# Relay_Board_Rev1-3_-_Altium.net
KiCad netlist of a schematic drawn in Altium Designer
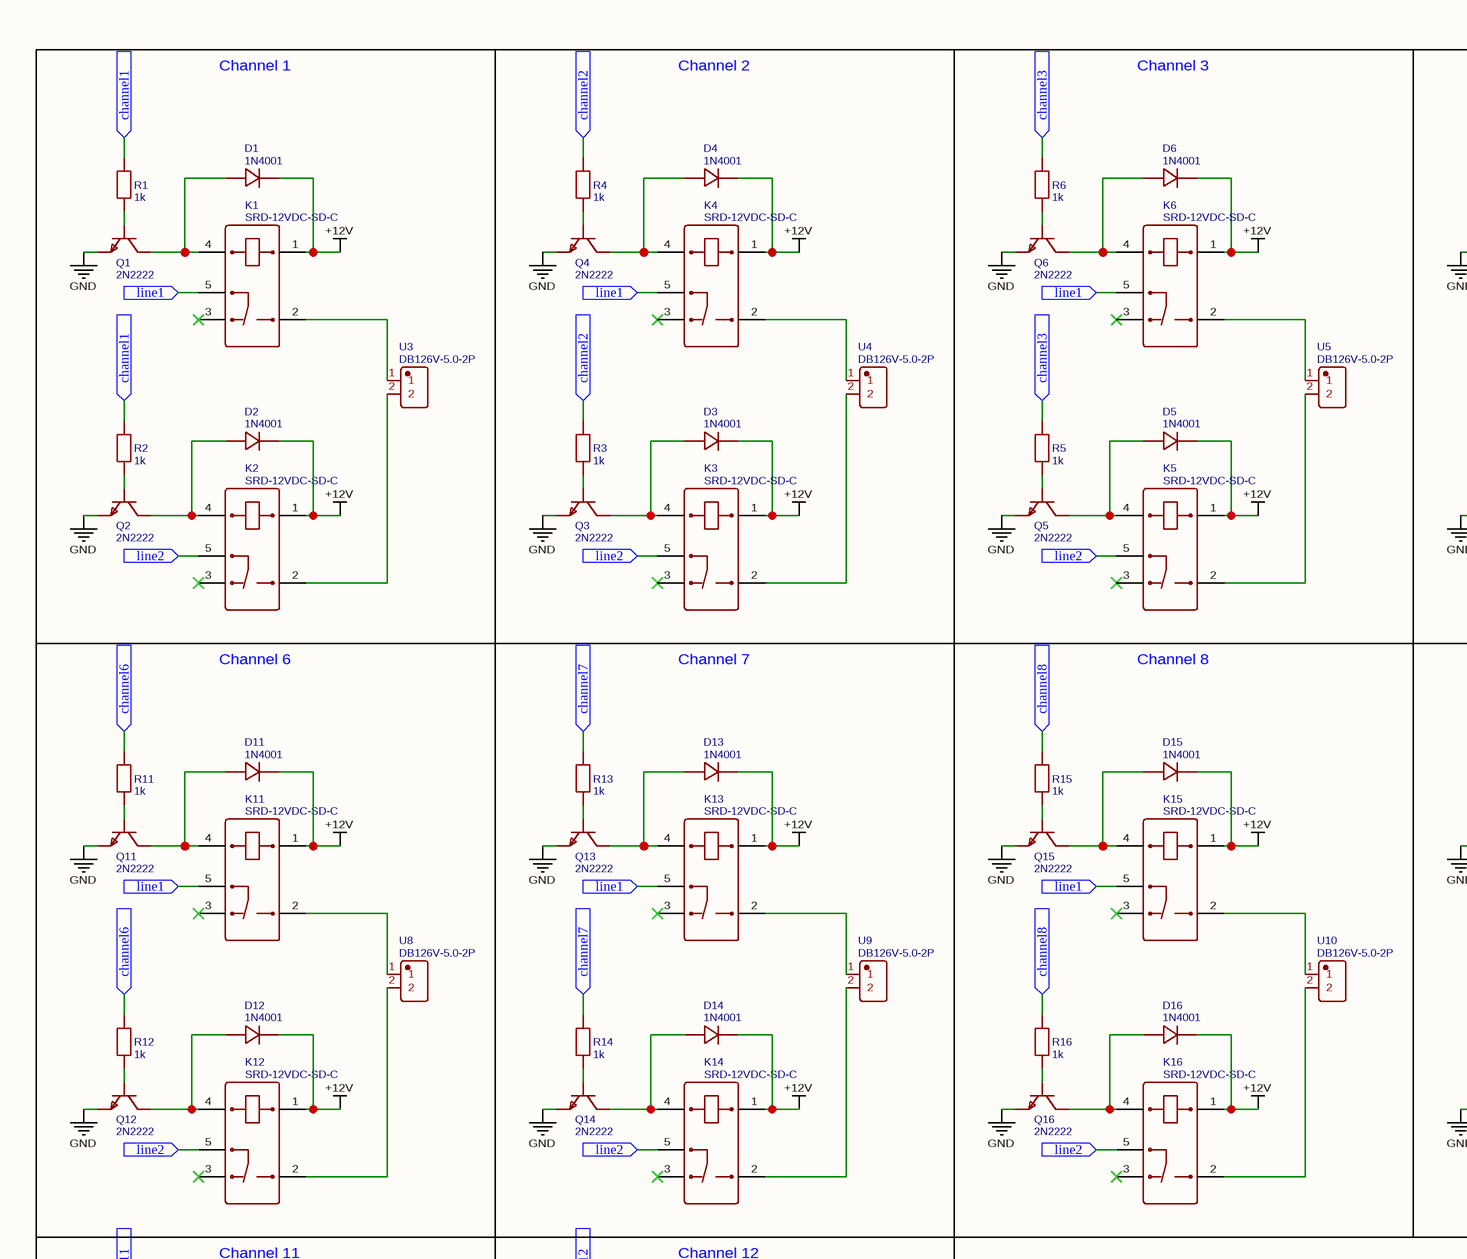
[diagram p0: Relay Board_Rev1-3 - Altium.schdoc, top left]
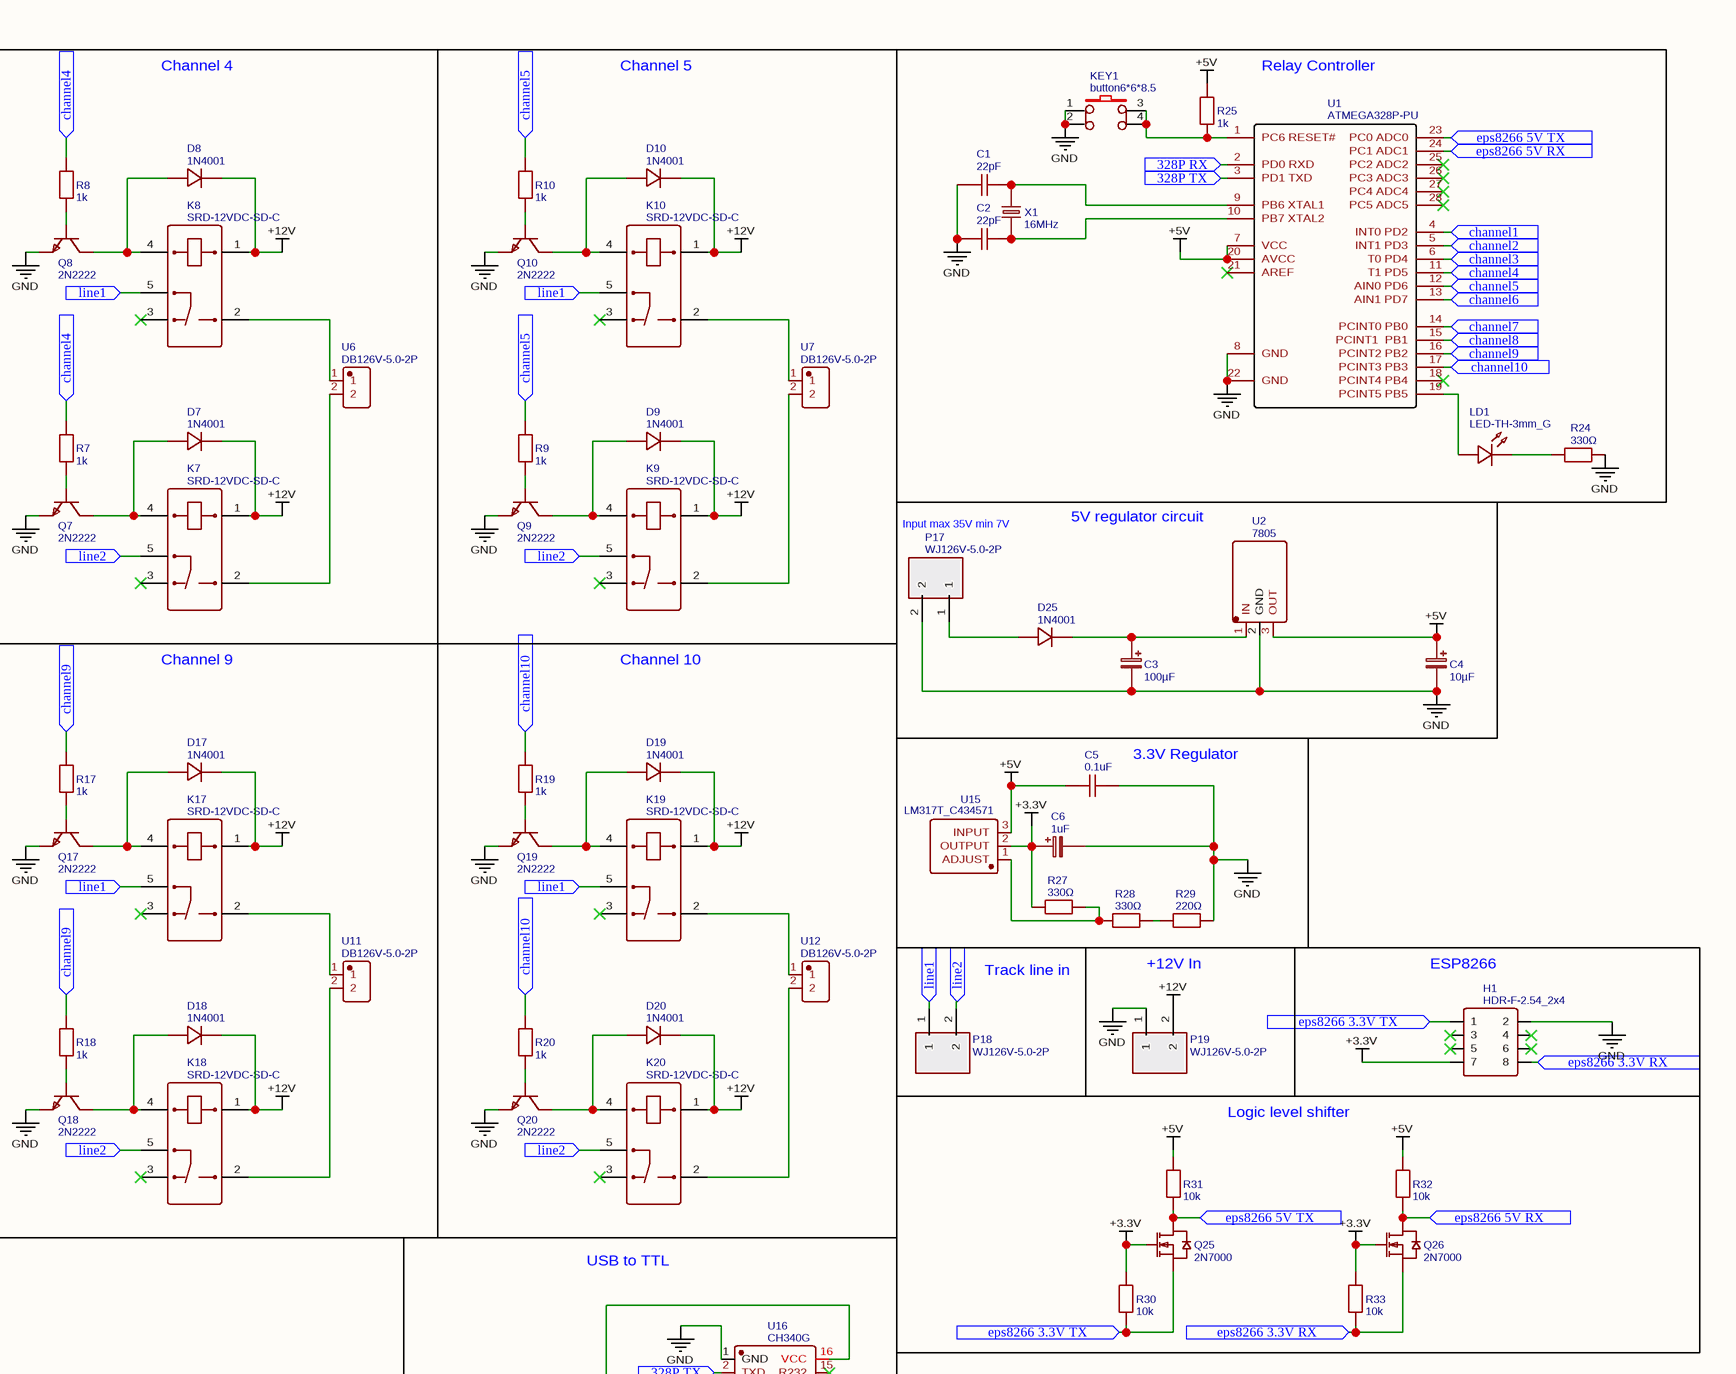
[diagram p1: Relay Board_Rev1-3 - Altium.schdoc, top right]
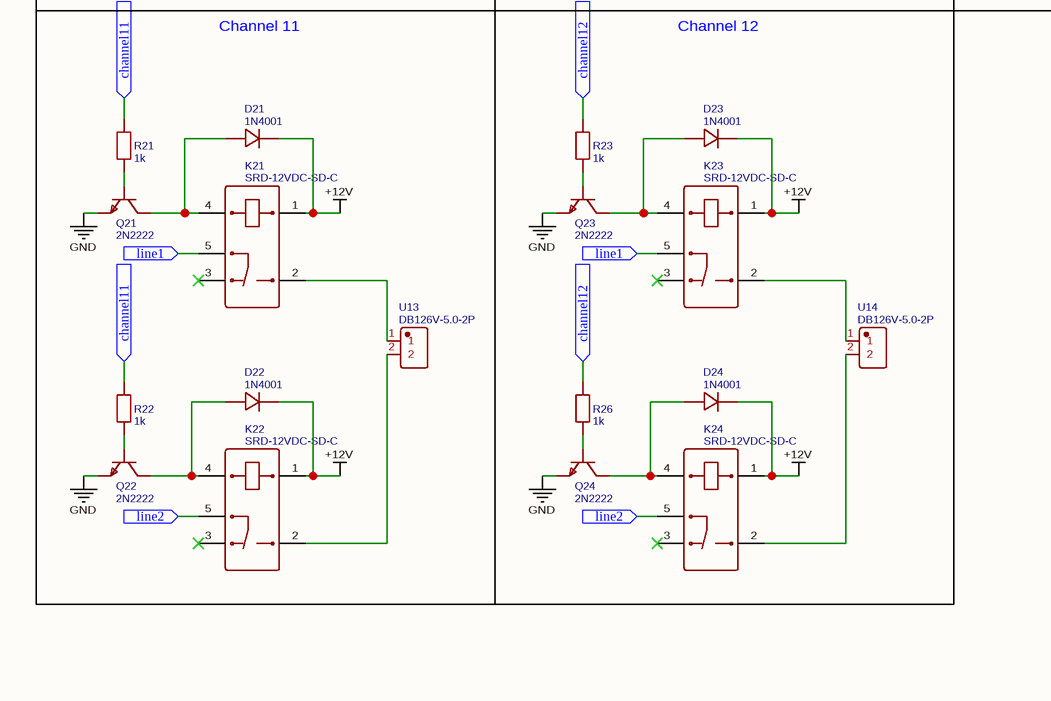
[diagram p2: Relay Board_Rev1-3 - Altium.schdoc, bottom left]
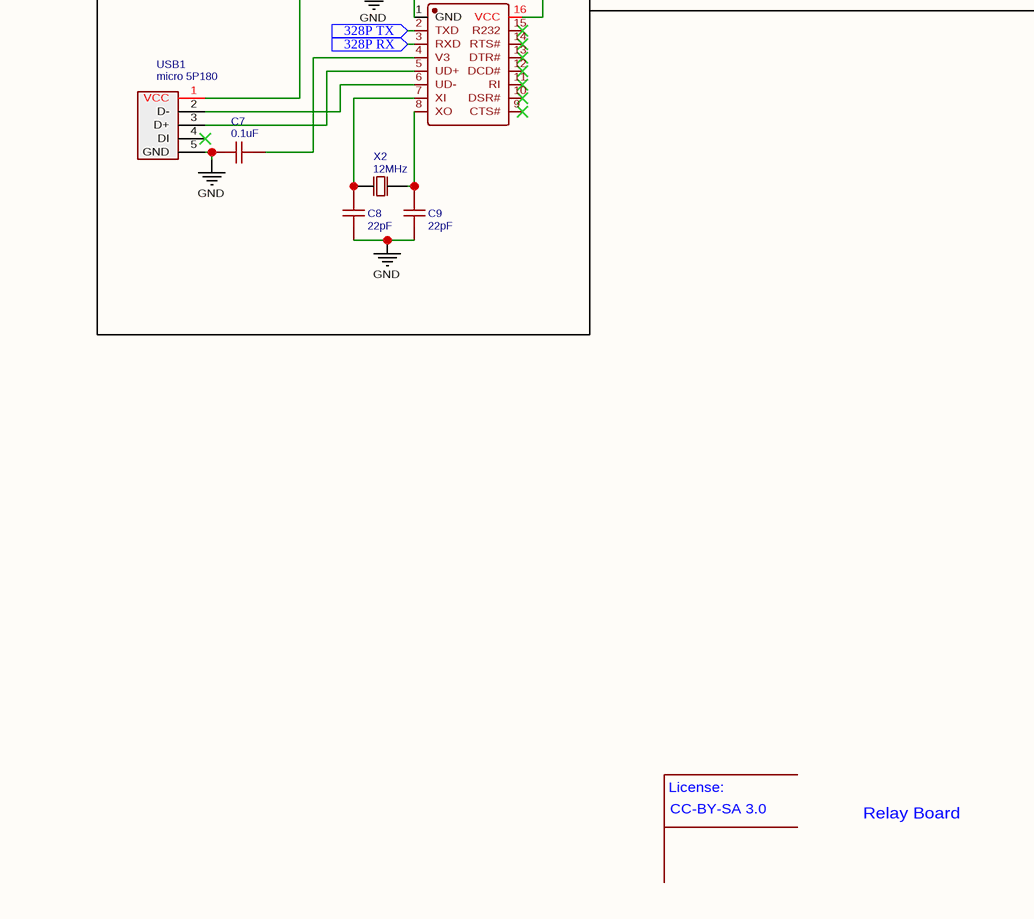
[diagram p3: Relay Board_Rev1-3 - Altium.schdoc, bottom right]

(export (version "E")
  (design (tool "Eeschema 10.0.6"))
  (components
    (comp (ref "C1")
      (value "22pF")
      (fields (field (name "CONTRIBUTOR") "LCEDA_Lib"))
      (libsource (lib "altium-import") (part "root_0_22pF_"))
    )
    (comp (ref "C2")
      (value "22pF")
      (fields (field (name "CONTRIBUTOR") "LCEDA_Lib"))
      (libsource (lib "altium-import") (part "root_0_22pF_"))
    )
    (comp (ref "C3")
      (value "100µF")
      (fields (field (name "CONTRIBUTOR") "LCEDA_Lib"))
      (libsource (lib "altium-import") (part "root_3_100µF_"))
    )
    (comp (ref "C4")
      (value "10µF")
      (fields (field (name "CONTRIBUTOR") "LCEDA_Lib"))
      (libsource (lib "altium-import") (part "root_3_10µF_"))
    )
    (comp (ref "C5")
      (value "0.1uF")
      (fields (field (name "CONTRIBUTOR") "LCEDA_Lib"))
      (libsource (lib "altium-import") (part "root_2_0.1uF_"))
    )
    (comp (ref "C6")
      (value "1uF")
      (fields (field (name "CONTRIBUTOR") "LCEDA_Lib"))
      (libsource (lib "altium-import") (part "root_0_1uF_"))
    )
    (comp (ref "C7")
      (value "0.1uF")
      (fields (field (name "CONTRIBUTOR") "LCEDA_Lib"))
      (libsource (lib "altium-import") (part "root_2_0.1uF_"))
    )
    (comp (ref "C8")
      (value "22pF")
      (fields (field (name "CONTRIBUTOR") "LCEDA_Lib"))
      (libsource (lib "altium-import") (part "root_1_22pF_"))
    )
    (comp (ref "C9")
      (value "22pF")
      (fields (field (name "CONTRIBUTOR") "LCEDA_Lib"))
      (libsource (lib "altium-import") (part "root_1_22pF_"))
    )
    (comp (ref "D1")
      (value "1N4001")
      (fields (field (name "BOM_SUPPLIER PART") "C82804"))
      (libsource (lib "altium-import") (part "root_2_1N4001_"))
    )
    (comp (ref "D2")
      (value "1N4001")
      (fields (field (name "BOM_SUPPLIER PART") "C82804"))
      (libsource (lib "altium-import") (part "root_2_1N4001_"))
    )
    (comp (ref "D3")
      (value "1N4001")
      (fields (field (name "BOM_SUPPLIER PART") "C82804"))
      (libsource (lib "altium-import") (part "root_2_1N4001_"))
    )
    (comp (ref "D4")
      (value "1N4001")
      (fields (field (name "BOM_SUPPLIER PART") "C82804"))
      (libsource (lib "altium-import") (part "root_2_1N4001_"))
    )
    (comp (ref "D5")
      (value "1N4001")
      (fields (field (name "BOM_SUPPLIER PART") "C82804"))
      (libsource (lib "altium-import") (part "root_2_1N4001_"))
    )
    (comp (ref "D6")
      (value "1N4001")
      (fields (field (name "BOM_SUPPLIER PART") "C82804"))
      (libsource (lib "altium-import") (part "root_2_1N4001_"))
    )
    (comp (ref "D7")
      (value "1N4001")
      (fields (field (name "BOM_SUPPLIER PART") "C82804"))
      (libsource (lib "altium-import") (part "root_2_1N4001_"))
    )
    (comp (ref "D8")
      (value "1N4001")
      (fields (field (name "BOM_SUPPLIER PART") "C82804"))
      (libsource (lib "altium-import") (part "root_2_1N4001_"))
    )
    (comp (ref "D9")
      (value "1N4001")
      (fields (field (name "BOM_SUPPLIER PART") "C82804"))
      (libsource (lib "altium-import") (part "root_2_1N4001_"))
    )
    (comp (ref "D10")
      (value "1N4001")
      (fields (field (name "BOM_SUPPLIER PART") "C82804"))
      (libsource (lib "altium-import") (part "root_2_1N4001_"))
    )
    (comp (ref "D11")
      (value "1N4001")
      (fields (field (name "BOM_SUPPLIER PART") "C82804"))
      (libsource (lib "altium-import") (part "root_2_1N4001_"))
    )
    (comp (ref "D12")
      (value "1N4001")
      (fields (field (name "BOM_SUPPLIER PART") "C82804"))
      (libsource (lib "altium-import") (part "root_2_1N4001_"))
    )
    (comp (ref "D13")
      (value "1N4001")
      (fields (field (name "BOM_SUPPLIER PART") "C82804"))
      (libsource (lib "altium-import") (part "root_2_1N4001_"))
    )
    (comp (ref "D14")
      (value "1N4001")
      (fields (field (name "BOM_SUPPLIER PART") "C82804"))
      (libsource (lib "altium-import") (part "root_2_1N4001_"))
    )
    (comp (ref "D15")
      (value "1N4001")
      (fields (field (name "BOM_SUPPLIER PART") "C82804"))
      (libsource (lib "altium-import") (part "root_2_1N4001_"))
    )
    (comp (ref "D16")
      (value "1N4001")
      (fields (field (name "BOM_SUPPLIER PART") "C82804"))
      (libsource (lib "altium-import") (part "root_2_1N4001_"))
    )
    (comp (ref "D17")
      (value "1N4001")
      (fields (field (name "BOM_SUPPLIER PART") "C82804"))
      (libsource (lib "altium-import") (part "root_2_1N4001_"))
    )
    (comp (ref "D18")
      (value "1N4001")
      (fields (field (name "BOM_SUPPLIER PART") "C82804"))
      (libsource (lib "altium-import") (part "root_2_1N4001_"))
    )
    (comp (ref "D19")
      (value "1N4001")
      (fields (field (name "BOM_SUPPLIER PART") "C82804"))
      (libsource (lib "altium-import") (part "root_2_1N4001_"))
    )
    (comp (ref "D20")
      (value "1N4001")
      (fields (field (name "BOM_SUPPLIER PART") "C82804"))
      (libsource (lib "altium-import") (part "root_2_1N4001_"))
    )
    (comp (ref "D21")
      (value "1N4001")
      (fields (field (name "BOM_SUPPLIER PART") "C82804"))
      (libsource (lib "altium-import") (part "root_2_1N4001_"))
    )
    (comp (ref "D22")
      (value "1N4001")
      (fields (field (name "BOM_SUPPLIER PART") "C82804"))
      (libsource (lib "altium-import") (part "root_2_1N4001_"))
    )
    (comp (ref "D23")
      (value "1N4001")
      (fields (field (name "BOM_SUPPLIER PART") "C82804"))
      (libsource (lib "altium-import") (part "root_2_1N4001_"))
    )
    (comp (ref "D24")
      (value "1N4001")
      (fields (field (name "BOM_SUPPLIER PART") "C82804"))
      (libsource (lib "altium-import") (part "root_2_1N4001_"))
    )
    (comp (ref "D25")
      (value "1N4001")
      (fields (field (name "BOM_SUPPLIER PART") "C82804"))
      (libsource (lib "altium-import") (part "root_2_1N4001_"))
    )
    (comp (ref "H1")
      (value "HDR-F-2.54_2x4")
      (fields (field (name "BOM_SUPPLIER PART") "C239344") (field (name "CONTRIBUTOR") "LCEDA_Lib"))
      (libsource (lib "altium-import") (part "root_0_HDR-F-2.54_2x4_"))
    )
    (comp (ref "K1")
      (value "SRD-12VDC-SD-C")
      (fields (field (name "BOM_SUPPLIER PART") "C247843") (field (name "CONTRIBUTOR") "LCSC"))
      (libsource (lib "altium-import") (part "root_2_SRD-12VDC-SD-C_"))
    )
    (comp (ref "K2")
      (value "SRD-12VDC-SD-C")
      (fields (field (name "BOM_SUPPLIER PART") "C247843") (field (name "CONTRIBUTOR") "LCSC"))
      (libsource (lib "altium-import") (part "root_2_SRD-12VDC-SD-C_"))
    )
    (comp (ref "K3")
      (value "SRD-12VDC-SD-C")
      (fields (field (name "BOM_SUPPLIER PART") "C247843") (field (name "CONTRIBUTOR") "LCSC"))
      (libsource (lib "altium-import") (part "root_2_SRD-12VDC-SD-C_"))
    )
    (comp (ref "K4")
      (value "SRD-12VDC-SD-C")
      (fields (field (name "BOM_SUPPLIER PART") "C247843") (field (name "CONTRIBUTOR") "LCSC"))
      (libsource (lib "altium-import") (part "root_2_SRD-12VDC-SD-C_"))
    )
    (comp (ref "K5")
      (value "SRD-12VDC-SD-C")
      (fields (field (name "BOM_SUPPLIER PART") "C247843") (field (name "CONTRIBUTOR") "LCSC"))
      (libsource (lib "altium-import") (part "root_2_SRD-12VDC-SD-C_"))
    )
    (comp (ref "K6")
      (value "SRD-12VDC-SD-C")
      (fields (field (name "BOM_SUPPLIER PART") "C247843") (field (name "CONTRIBUTOR") "LCSC"))
      (libsource (lib "altium-import") (part "root_2_SRD-12VDC-SD-C_"))
    )
    (comp (ref "K7")
      (value "SRD-12VDC-SD-C")
      (fields (field (name "BOM_SUPPLIER PART") "C247843") (field (name "CONTRIBUTOR") "LCSC"))
      (libsource (lib "altium-import") (part "root_2_SRD-12VDC-SD-C_"))
    )
    (comp (ref "K8")
      (value "SRD-12VDC-SD-C")
      (fields (field (name "BOM_SUPPLIER PART") "C247843") (field (name "CONTRIBUTOR") "LCSC"))
      (libsource (lib "altium-import") (part "root_2_SRD-12VDC-SD-C_"))
    )
    (comp (ref "K9")
      (value "SRD-12VDC-SD-C")
      (fields (field (name "BOM_SUPPLIER PART") "C247843") (field (name "CONTRIBUTOR") "LCSC"))
      (libsource (lib "altium-import") (part "root_2_SRD-12VDC-SD-C_"))
    )
    (comp (ref "K10")
      (value "SRD-12VDC-SD-C")
      (fields (field (name "BOM_SUPPLIER PART") "C247843") (field (name "CONTRIBUTOR") "LCSC"))
      (libsource (lib "altium-import") (part "root_2_SRD-12VDC-SD-C_"))
    )
    (comp (ref "K11")
      (value "SRD-12VDC-SD-C")
      (fields (field (name "BOM_SUPPLIER PART") "C247843") (field (name "CONTRIBUTOR") "LCSC"))
      (libsource (lib "altium-import") (part "root_2_SRD-12VDC-SD-C_"))
    )
    (comp (ref "K12")
      (value "SRD-12VDC-SD-C")
      (fields (field (name "BOM_SUPPLIER PART") "C247843") (field (name "CONTRIBUTOR") "LCSC"))
      (libsource (lib "altium-import") (part "root_2_SRD-12VDC-SD-C_"))
    )
    (comp (ref "K13")
      (value "SRD-12VDC-SD-C")
      (fields (field (name "BOM_SUPPLIER PART") "C247843") (field (name "CONTRIBUTOR") "LCSC"))
      (libsource (lib "altium-import") (part "root_2_SRD-12VDC-SD-C_"))
    )
    (comp (ref "K14")
      (value "SRD-12VDC-SD-C")
      (fields (field (name "BOM_SUPPLIER PART") "C247843") (field (name "CONTRIBUTOR") "LCSC"))
      (libsource (lib "altium-import") (part "root_2_SRD-12VDC-SD-C_"))
    )
    (comp (ref "K15")
      (value "SRD-12VDC-SD-C")
      (fields (field (name "BOM_SUPPLIER PART") "C247843") (field (name "CONTRIBUTOR") "LCSC"))
      (libsource (lib "altium-import") (part "root_2_SRD-12VDC-SD-C_"))
    )
    (comp (ref "K16")
      (value "SRD-12VDC-SD-C")
      (fields (field (name "BOM_SUPPLIER PART") "C247843") (field (name "CONTRIBUTOR") "LCSC"))
      (libsource (lib "altium-import") (part "root_2_SRD-12VDC-SD-C_"))
    )
    (comp (ref "K17")
      (value "SRD-12VDC-SD-C")
      (fields (field (name "BOM_SUPPLIER PART") "C247843") (field (name "CONTRIBUTOR") "LCSC"))
      (libsource (lib "altium-import") (part "root_2_SRD-12VDC-SD-C_"))
    )
    (comp (ref "K18")
      (value "SRD-12VDC-SD-C")
      (fields (field (name "BOM_SUPPLIER PART") "C247843") (field (name "CONTRIBUTOR") "LCSC"))
      (libsource (lib "altium-import") (part "root_2_SRD-12VDC-SD-C_"))
    )
    (comp (ref "K19")
      (value "SRD-12VDC-SD-C")
      (fields (field (name "BOM_SUPPLIER PART") "C247843") (field (name "CONTRIBUTOR") "LCSC"))
      (libsource (lib "altium-import") (part "root_2_SRD-12VDC-SD-C_"))
    )
    (comp (ref "K20")
      (value "SRD-12VDC-SD-C")
      (fields (field (name "BOM_SUPPLIER PART") "C247843") (field (name "CONTRIBUTOR") "LCSC"))
      (libsource (lib "altium-import") (part "root_2_SRD-12VDC-SD-C_"))
    )
    (comp (ref "K21")
      (value "SRD-12VDC-SD-C")
      (fields (field (name "BOM_SUPPLIER PART") "C247843") (field (name "CONTRIBUTOR") "LCSC"))
      (libsource (lib "altium-import") (part "root_2_SRD-12VDC-SD-C_"))
    )
    (comp (ref "K22")
      (value "SRD-12VDC-SD-C")
      (fields (field (name "BOM_SUPPLIER PART") "C247843") (field (name "CONTRIBUTOR") "LCSC"))
      (libsource (lib "altium-import") (part "root_2_SRD-12VDC-SD-C_"))
    )
    (comp (ref "K23")
      (value "SRD-12VDC-SD-C")
      (fields (field (name "BOM_SUPPLIER PART") "C247843") (field (name "CONTRIBUTOR") "LCSC"))
      (libsource (lib "altium-import") (part "root_2_SRD-12VDC-SD-C_"))
    )
    (comp (ref "K24")
      (value "SRD-12VDC-SD-C")
      (fields (field (name "BOM_SUPPLIER PART") "C247843") (field (name "CONTRIBUTOR") "LCSC"))
      (libsource (lib "altium-import") (part "root_2_SRD-12VDC-SD-C_"))
    )
    (comp (ref "KEY1")
      (value "button6*6*8.5")
      (fields (field (name "BOM_SUPPLIER PART") "C59980"))
      (libsource (lib "altium-import") (part "root_0_button6*6*8.5_"))
    )
    (comp (ref "LD1")
      (value "LED-TH-3mm_G")
      (fields
        (field (name "BOM_MANUFACTURER PART") "204-10SYGD/S530-E3")
        (field (name "BOM_SUPPLIER PART") "C85161")
        (field (name "CONTRIBUTOR") "LCEDA_Lib")
      )
      (libsource (lib "altium-import") (part "root_0_LED-TH-3mm_G_"))
    )
    (comp (ref "P17")
      (value "WJ126V-5.0-2P")
      (fields (field (name "BOM_SUPPLIER PART") "C8404"))
      (libsource (lib "altium-import") (part "root_3_WJ126V-5.0-2P_"))
    )
    (comp (ref "P18")
      (value "WJ126V-5.0-2P")
      (fields (field (name "BOM_SUPPLIER PART") "C8404"))
      (libsource (lib "altium-import") (part "root_1_WJ126V-5.0-2P_"))
    )
    (comp (ref "P19")
      (value "WJ126V-5.0-2P")
      (fields (field (name "BOM_SUPPLIER PART") "C8404"))
      (libsource (lib "altium-import") (part "root_1_WJ126V-5.0-2P_"))
    )
    (comp (ref "Q1")
      (value "2N2222")
      (fields (field (name "BOM_SUPPLIER PART") "C118536") (field (name "CONTRIBUTOR") "LCSC"))
      (libsource (lib "altium-import") (part "root_3_2N2222_"))
    )
    (comp (ref "Q2")
      (value "2N2222")
      (fields (field (name "BOM_SUPPLIER PART") "C118536") (field (name "CONTRIBUTOR") "LCSC"))
      (libsource (lib "altium-import") (part "root_3_2N2222_"))
    )
    (comp (ref "Q3")
      (value "2N2222")
      (fields (field (name "BOM_SUPPLIER PART") "C118536") (field (name "CONTRIBUTOR") "LCSC"))
      (libsource (lib "altium-import") (part "root_3_2N2222_"))
    )
    (comp (ref "Q4")
      (value "2N2222")
      (fields (field (name "BOM_SUPPLIER PART") "C118536") (field (name "CONTRIBUTOR") "LCSC"))
      (libsource (lib "altium-import") (part "root_3_2N2222_"))
    )
    (comp (ref "Q5")
      (value "2N2222")
      (fields (field (name "BOM_SUPPLIER PART") "C118536") (field (name "CONTRIBUTOR") "LCSC"))
      (libsource (lib "altium-import") (part "root_3_2N2222_"))
    )
    (comp (ref "Q6")
      (value "2N2222")
      (fields (field (name "BOM_SUPPLIER PART") "C118536") (field (name "CONTRIBUTOR") "LCSC"))
      (libsource (lib "altium-import") (part "root_3_2N2222_"))
    )
    (comp (ref "Q7")
      (value "2N2222")
      (fields (field (name "BOM_SUPPLIER PART") "C118536") (field (name "CONTRIBUTOR") "LCSC"))
      (libsource (lib "altium-import") (part "root_3_2N2222_"))
    )
    (comp (ref "Q8")
      (value "2N2222")
      (fields (field (name "BOM_SUPPLIER PART") "C118536") (field (name "CONTRIBUTOR") "LCSC"))
      (libsource (lib "altium-import") (part "root_3_2N2222_"))
    )
    (comp (ref "Q9")
      (value "2N2222")
      (fields (field (name "BOM_SUPPLIER PART") "C118536") (field (name "CONTRIBUTOR") "LCSC"))
      (libsource (lib "altium-import") (part "root_3_2N2222_"))
    )
    (comp (ref "Q10")
      (value "2N2222")
      (fields (field (name "BOM_SUPPLIER PART") "C118536") (field (name "CONTRIBUTOR") "LCSC"))
      (libsource (lib "altium-import") (part "root_3_2N2222_"))
    )
    (comp (ref "Q11")
      (value "2N2222")
      (fields (field (name "BOM_SUPPLIER PART") "C118536") (field (name "CONTRIBUTOR") "LCSC"))
      (libsource (lib "altium-import") (part "root_3_2N2222_"))
    )
    (comp (ref "Q12")
      (value "2N2222")
      (fields (field (name "BOM_SUPPLIER PART") "C118536") (field (name "CONTRIBUTOR") "LCSC"))
      (libsource (lib "altium-import") (part "root_3_2N2222_"))
    )
    (comp (ref "Q13")
      (value "2N2222")
      (fields (field (name "BOM_SUPPLIER PART") "C118536") (field (name "CONTRIBUTOR") "LCSC"))
      (libsource (lib "altium-import") (part "root_3_2N2222_"))
    )
    (comp (ref "Q14")
      (value "2N2222")
      (fields (field (name "BOM_SUPPLIER PART") "C118536") (field (name "CONTRIBUTOR") "LCSC"))
      (libsource (lib "altium-import") (part "root_3_2N2222_"))
    )
    (comp (ref "Q15")
      (value "2N2222")
      (fields (field (name "BOM_SUPPLIER PART") "C118536") (field (name "CONTRIBUTOR") "LCSC"))
      (libsource (lib "altium-import") (part "root_3_2N2222_"))
    )
    (comp (ref "Q16")
      (value "2N2222")
      (fields (field (name "BOM_SUPPLIER PART") "C118536") (field (name "CONTRIBUTOR") "LCSC"))
      (libsource (lib "altium-import") (part "root_3_2N2222_"))
    )
    (comp (ref "Q17")
      (value "2N2222")
      (fields (field (name "BOM_SUPPLIER PART") "C118536") (field (name "CONTRIBUTOR") "LCSC"))
      (libsource (lib "altium-import") (part "root_3_2N2222_"))
    )
    (comp (ref "Q18")
      (value "2N2222")
      (fields (field (name "BOM_SUPPLIER PART") "C118536") (field (name "CONTRIBUTOR") "LCSC"))
      (libsource (lib "altium-import") (part "root_3_2N2222_"))
    )
    (comp (ref "Q19")
      (value "2N2222")
      (fields (field (name "BOM_SUPPLIER PART") "C118536") (field (name "CONTRIBUTOR") "LCSC"))
      (libsource (lib "altium-import") (part "root_3_2N2222_"))
    )
    (comp (ref "Q20")
      (value "2N2222")
      (fields (field (name "BOM_SUPPLIER PART") "C118536") (field (name "CONTRIBUTOR") "LCSC"))
      (libsource (lib "altium-import") (part "root_3_2N2222_"))
    )
    (comp (ref "Q21")
      (value "2N2222")
      (fields (field (name "BOM_SUPPLIER PART") "C118536") (field (name "CONTRIBUTOR") "LCSC"))
      (libsource (lib "altium-import") (part "root_3_2N2222_"))
    )
    (comp (ref "Q22")
      (value "2N2222")
      (fields (field (name "BOM_SUPPLIER PART") "C118536") (field (name "CONTRIBUTOR") "LCSC"))
      (libsource (lib "altium-import") (part "root_3_2N2222_"))
    )
    (comp (ref "Q23")
      (value "2N2222")
      (fields (field (name "BOM_SUPPLIER PART") "C118536") (field (name "CONTRIBUTOR") "LCSC"))
      (libsource (lib "altium-import") (part "root_3_2N2222_"))
    )
    (comp (ref "Q24")
      (value "2N2222")
      (fields (field (name "BOM_SUPPLIER PART") "C118536") (field (name "CONTRIBUTOR") "LCSC"))
      (libsource (lib "altium-import") (part "root_3_2N2222_"))
    )
    (comp (ref "Q25")
      (value "2N7000")
      (fields (field (name "BOM_SUPPLIER PART") "C9114"))
      (libsource (lib "altium-import") (part "root_0_2N7000_"))
    )
    (comp (ref "Q26")
      (value "2N7000")
      (fields (field (name "BOM_SUPPLIER PART") "C9114"))
      (libsource (lib "altium-import") (part "root_0_2N7000_"))
    )
    (comp (ref "R1")
      (value "1k")
      (fields (field (name "CONTRIBUTOR") "LCEDA_Lib"))
      (libsource (lib "altium-import") (part "root_1_1k_"))
    )
    (comp (ref "R2")
      (value "1k")
      (fields (field (name "CONTRIBUTOR") "LCEDA_Lib"))
      (libsource (lib "altium-import") (part "root_1_1k_"))
    )
    (comp (ref "R3")
      (value "1k")
      (fields (field (name "CONTRIBUTOR") "LCEDA_Lib"))
      (libsource (lib "altium-import") (part "root_1_1k_"))
    )
    (comp (ref "R4")
      (value "1k")
      (fields (field (name "CONTRIBUTOR") "LCEDA_Lib"))
      (libsource (lib "altium-import") (part "root_1_1k_"))
    )
    (comp (ref "R5")
      (value "1k")
      (fields (field (name "CONTRIBUTOR") "LCEDA_Lib"))
      (libsource (lib "altium-import") (part "root_1_1k_"))
    )
    (comp (ref "R6")
      (value "1k")
      (fields (field (name "CONTRIBUTOR") "LCEDA_Lib"))
      (libsource (lib "altium-import") (part "root_1_1k_"))
    )
    (comp (ref "R7")
      (value "1k")
      (fields (field (name "CONTRIBUTOR") "LCEDA_Lib"))
      (libsource (lib "altium-import") (part "root_1_1k_"))
    )
    (comp (ref "R8")
      (value "1k")
      (fields (field (name "CONTRIBUTOR") "LCEDA_Lib"))
      (libsource (lib "altium-import") (part "root_1_1k_"))
    )
    (comp (ref "R9")
      (value "1k")
      (fields (field (name "CONTRIBUTOR") "LCEDA_Lib"))
      (libsource (lib "altium-import") (part "root_1_1k_"))
    )
    (comp (ref "R10")
      (value "1k")
      (fields (field (name "CONTRIBUTOR") "LCEDA_Lib"))
      (libsource (lib "altium-import") (part "root_1_1k_"))
    )
    (comp (ref "R11")
      (value "1k")
      (fields (field (name "CONTRIBUTOR") "LCEDA_Lib"))
      (libsource (lib "altium-import") (part "root_1_1k_"))
    )
    (comp (ref "R12")
      (value "1k")
      (fields (field (name "CONTRIBUTOR") "LCEDA_Lib"))
      (libsource (lib "altium-import") (part "root_1_1k_"))
    )
    (comp (ref "R13")
      (value "1k")
      (fields (field (name "CONTRIBUTOR") "LCEDA_Lib"))
      (libsource (lib "altium-import") (part "root_1_1k_"))
    )
    (comp (ref "R14")
      (value "1k")
      (fields (field (name "CONTRIBUTOR") "LCEDA_Lib"))
      (libsource (lib "altium-import") (part "root_1_1k_"))
    )
    (comp (ref "R15")
      (value "1k")
      (fields (field (name "CONTRIBUTOR") "LCEDA_Lib"))
      (libsource (lib "altium-import") (part "root_1_1k_"))
    )
    (comp (ref "R16")
      (value "1k")
      (fields (field (name "CONTRIBUTOR") "LCEDA_Lib"))
      (libsource (lib "altium-import") (part "root_1_1k_"))
    )
    (comp (ref "R17")
      (value "1k")
      (fields (field (name "CONTRIBUTOR") "LCEDA_Lib"))
      (libsource (lib "altium-import") (part "root_1_1k_"))
    )
    (comp (ref "R18")
      (value "1k")
      (fields (field (name "CONTRIBUTOR") "LCEDA_Lib"))
      (libsource (lib "altium-import") (part "root_1_1k_"))
    )
    (comp (ref "R19")
      (value "1k")
      (fields (field (name "CONTRIBUTOR") "LCEDA_Lib"))
      (libsource (lib "altium-import") (part "root_1_1k_"))
    )
    (comp (ref "R20")
      (value "1k")
      (fields (field (name "CONTRIBUTOR") "LCEDA_Lib"))
      (libsource (lib "altium-import") (part "root_1_1k_"))
    )
    (comp (ref "R21")
      (value "1k")
      (fields (field (name "CONTRIBUTOR") "LCEDA_Lib"))
      (libsource (lib "altium-import") (part "root_1_1k_"))
    )
    (comp (ref "R22")
      (value "1k")
      (fields (field (name "CONTRIBUTOR") "LCEDA_Lib"))
      (libsource (lib "altium-import") (part "root_1_1k_"))
    )
    (comp (ref "R23")
      (value "1k")
      (fields (field (name "CONTRIBUTOR") "LCEDA_Lib"))
      (libsource (lib "altium-import") (part "root_1_1k_"))
    )
    (comp (ref "R24")
      (value "330Ω")
      (fields (field (name "CONTRIBUTOR") "LCEDA_Lib"))
      (libsource (lib "altium-import") (part "root_0_330Ω_"))
    )
    (comp (ref "R25")
      (value "1k")
      (fields (field (name "CONTRIBUTOR") "LCEDA_Lib"))
      (libsource (lib "altium-import") (part "root_1_1k_"))
    )
    (comp (ref "R26")
      (value "1k")
      (fields (field (name "CONTRIBUTOR") "LCEDA_Lib"))
      (libsource (lib "altium-import") (part "root_1_1k_"))
    )
    (comp (ref "R27")
      (value "330Ω")
      (fields (field (name "CONTRIBUTOR") "LCEDA_Lib"))
      (libsource (lib "altium-import") (part "root_2_330Ω_"))
    )
    (comp (ref "R28")
      (value "330Ω")
      (fields (field (name "CONTRIBUTOR") "LCEDA_Lib"))
      (libsource (lib "altium-import") (part "root_0_330Ω_"))
    )
    (comp (ref "R29")
      (value "220Ω")
      (fields (field (name "CONTRIBUTOR") "LCEDA_Lib"))
      (libsource (lib "altium-import") (part "root_0_220Ω_"))
    )
    (comp (ref "R30")
      (value "10k")
      (fields (field (name "CONTRIBUTOR") "LCEDA_Lib"))
      (libsource (lib "altium-import") (part "root_1_10k_"))
    )
    (comp (ref "R31")
      (value "10k")
      (fields (field (name "CONTRIBUTOR") "LCEDA_Lib"))
      (libsource (lib "altium-import") (part "root_1_10k_"))
    )
    (comp (ref "R32")
      (value "10k")
      (fields (field (name "CONTRIBUTOR") "LCEDA_Lib"))
      (libsource (lib "altium-import") (part "root_1_10k_"))
    )
    (comp (ref "R33")
      (value "10k")
      (fields (field (name "CONTRIBUTOR") "LCEDA_Lib"))
      (libsource (lib "altium-import") (part "root_1_10k_"))
    )
    (comp (ref "U1")
      (value "ATMEGA328P-PU")
      (fields (field (name "BOM_SUPPLIER PART") "C33901") (field (name "CONTRIBUTOR") "LCSC"))
      (libsource (lib "altium-import") (part "root_0_ATMEGA328P-PU_"))
    )
    (comp (ref "U2")
      (value "7805")
      (fields (field (name "BOM_SUPPLIER PART") "C305416") (field (name "CONTRIBUTOR") "LCSC"))
      (libsource (lib "altium-import") (part "root_1_7805_"))
    )
    (comp (ref "U3")
      (value "DB126V-5.0-2P")
      (fields (field (name "BOM_SUPPLIER PART") "C395849") (field (name "CONTRIBUTOR") "LCSC"))
      (libsource (lib "altium-import") (part "root_0_DB126V-5.0-2P_"))
    )
    (comp (ref "U4")
      (value "DB126V-5.0-2P")
      (fields (field (name "BOM_SUPPLIER PART") "C395849") (field (name "CONTRIBUTOR") "LCSC"))
      (libsource (lib "altium-import") (part "root_0_DB126V-5.0-2P_"))
    )
    (comp (ref "U5")
      (value "DB126V-5.0-2P")
      (fields (field (name "BOM_SUPPLIER PART") "C395849") (field (name "CONTRIBUTOR") "LCSC"))
      (libsource (lib "altium-import") (part "root_0_DB126V-5.0-2P_"))
    )
    (comp (ref "U6")
      (value "DB126V-5.0-2P")
      (fields (field (name "BOM_SUPPLIER PART") "C395849") (field (name "CONTRIBUTOR") "LCSC"))
      (libsource (lib "altium-import") (part "root_0_DB126V-5.0-2P_"))
    )
    (comp (ref "U7")
      (value "DB126V-5.0-2P")
      (fields (field (name "BOM_SUPPLIER PART") "C395849") (field (name "CONTRIBUTOR") "LCSC"))
      (libsource (lib "altium-import") (part "root_0_DB126V-5.0-2P_"))
    )
    (comp (ref "U8")
      (value "DB126V-5.0-2P")
      (fields (field (name "BOM_SUPPLIER PART") "C395849") (field (name "CONTRIBUTOR") "LCSC"))
      (libsource (lib "altium-import") (part "root_0_DB126V-5.0-2P_"))
    )
    (comp (ref "U9")
      (value "DB126V-5.0-2P")
      (fields (field (name "BOM_SUPPLIER PART") "C395849") (field (name "CONTRIBUTOR") "LCSC"))
      (libsource (lib "altium-import") (part "root_0_DB126V-5.0-2P_"))
    )
    (comp (ref "U10")
      (value "DB126V-5.0-2P")
      (fields (field (name "BOM_SUPPLIER PART") "C395849") (field (name "CONTRIBUTOR") "LCSC"))
      (libsource (lib "altium-import") (part "root_0_DB126V-5.0-2P_"))
    )
    (comp (ref "U11")
      (value "DB126V-5.0-2P")
      (fields (field (name "BOM_SUPPLIER PART") "C395849") (field (name "CONTRIBUTOR") "LCSC"))
      (libsource (lib "altium-import") (part "root_0_DB126V-5.0-2P_"))
    )
    (comp (ref "U12")
      (value "DB126V-5.0-2P")
      (fields (field (name "BOM_SUPPLIER PART") "C395849") (field (name "CONTRIBUTOR") "LCSC"))
      (libsource (lib "altium-import") (part "root_0_DB126V-5.0-2P_"))
    )
    (comp (ref "U13")
      (value "DB126V-5.0-2P")
      (fields (field (name "BOM_SUPPLIER PART") "C395849") (field (name "CONTRIBUTOR") "LCSC"))
      (libsource (lib "altium-import") (part "root_0_DB126V-5.0-2P_"))
    )
    (comp (ref "U14")
      (value "DB126V-5.0-2P")
      (fields (field (name "BOM_SUPPLIER PART") "C395849") (field (name "CONTRIBUTOR") "LCSC"))
      (libsource (lib "altium-import") (part "root_0_DB126V-5.0-2P_"))
    )
    (comp (ref "U15")
      (value "LM317T_C434571")
      (fields
        (field (name "BOM_SUPPLIER PART") "C434571")
        (field (name "BOM_MANUFACTURER PART") "LM317T")
        (field (name "CONTRIBUTOR") "LCSC")
      )
      (libsource (lib "altium-import") (part "root_2_LM317T_C434571_"))
    )
    (comp (ref "U16")
      (value "CH340G")
      (fields (field (name "BOM_SUPPLIER PART") "C14267"))
      (libsource (lib "altium-import") (part "root_0_CH340G_"))
    )
    (comp (ref "USB1")
      (value "micro 5P180")
      (fields (field (name "BOM_SUPPLIER PART") "C40941"))
      (libsource (lib "altium-import") (part "root_0_micro 5P180_"))
    )
    (comp (ref "X1")
      (value "16MHz")
      (fields
        (field (name "BOM_SUPPLIER PART") "C295075")
        (field (name "BOM_MANUFACTURER PART") "XIHCELNANF-16MHZ")
        (field (name "CONTRIBUTOR") "LCSC")
      )
      (libsource (lib "altium-import") (part "root_3_16MHz_"))
    )
    (comp (ref "X2")
      (value "12MHz")
      (fields
        (field (name "BOM_SUPPLIER PART") "C240914")
        (field (name "BOM_MANUFACTURER PART") "49S-12.00-20-20-20/A")
        (field (name "CONTRIBUTOR") "LCSC")
      )
      (libsource (lib "altium-import") (part "root_0_12MHz_"))
    )
  )
  (nets
    (net (code "1") (name "+3.3V") (class "Default")
      (node (ref "C6") (pin "1") (pinfunction "1_1") (pintype "passive"))
      (node (ref "H1") (pin "7") (pinfunction "7_7") (pintype "passive"))
      (node (ref "Q25") (pin "2") (pinfunction "G_2") (pintype "passive"))
      (node (ref "Q26") (pin "2") (pinfunction "G_2") (pintype "passive"))
      (node (ref "R27") (pin "2") (pinfunction "2_2") (pintype "passive"))
      (node (ref "R30") (pin "2") (pinfunction "2_2") (pintype "passive"))
      (node (ref "R33") (pin "2") (pinfunction "2_2") (pintype "passive"))
      (node (ref "U15") (pin "2") (pinfunction "OUTPUT_2") (pintype "passive"))
    )
    (net (code "2") (name "+5V") (class "Default")
      (node (ref "C4") (pin "1") (pinfunction "1_1") (pintype "passive"))
      (node (ref "C5") (pin "2") (pinfunction "2_2") (pintype "passive"))
      (node (ref "R25") (pin "2") (pinfunction "2_2") (pintype "passive"))
      (node (ref "R31") (pin "2") (pinfunction "2_2") (pintype "passive"))
      (node (ref "R32") (pin "2") (pinfunction "2_2") (pintype "passive"))
      (node (ref "U1") (pin "20") (pinfunction "AVCC_20") (pintype "passive"))
      (node (ref "U1") (pin "7") (pinfunction "VCC_7") (pintype "passive"))
      (node (ref "U15") (pin "3") (pinfunction "INPUT_3") (pintype "passive"))
      (node (ref "U2") (pin "3") (pinfunction "OUT_3") (pintype "passive"))
    )
    (net (code "3") (name "+12V") (class "Default")
      (node (ref "D1") (pin "1") (pinfunction "K_1") (pintype "passive"))
      (node (ref "D10") (pin "1") (pinfunction "K_1") (pintype "passive"))
      (node (ref "D11") (pin "1") (pinfunction "K_1") (pintype "passive"))
      (node (ref "D12") (pin "1") (pinfunction "K_1") (pintype "passive"))
      (node (ref "D13") (pin "1") (pinfunction "K_1") (pintype "passive"))
      (node (ref "D14") (pin "1") (pinfunction "K_1") (pintype "passive"))
      (node (ref "D15") (pin "1") (pinfunction "K_1") (pintype "passive"))
      (node (ref "D16") (pin "1") (pinfunction "K_1") (pintype "passive"))
      (node (ref "D17") (pin "1") (pinfunction "K_1") (pintype "passive"))
      (node (ref "D18") (pin "1") (pinfunction "K_1") (pintype "passive"))
      (node (ref "D19") (pin "1") (pinfunction "K_1") (pintype "passive"))
      (node (ref "D2") (pin "1") (pinfunction "K_1") (pintype "passive"))
      (node (ref "D20") (pin "1") (pinfunction "K_1") (pintype "passive"))
      (node (ref "D21") (pin "1") (pinfunction "K_1") (pintype "passive"))
      (node (ref "D22") (pin "1") (pinfunction "K_1") (pintype "passive"))
      (node (ref "D23") (pin "1") (pinfunction "K_1") (pintype "passive"))
      (node (ref "D24") (pin "1") (pinfunction "K_1") (pintype "passive"))
      (node (ref "D3") (pin "1") (pinfunction "K_1") (pintype "passive"))
      (node (ref "D4") (pin "1") (pinfunction "K_1") (pintype "passive"))
      (node (ref "D5") (pin "1") (pinfunction "K_1") (pintype "passive"))
      (node (ref "D6") (pin "1") (pinfunction "K_1") (pintype "passive"))
      (node (ref "D7") (pin "1") (pinfunction "K_1") (pintype "passive"))
      (node (ref "D8") (pin "1") (pinfunction "K_1") (pintype "passive"))
      (node (ref "D9") (pin "1") (pinfunction "K_1") (pintype "passive"))
      (node (ref "K1") (pin "1") (pinfunction "1_1") (pintype "passive"))
      (node (ref "K10") (pin "1") (pinfunction "1_1") (pintype "passive"))
      (node (ref "K11") (pin "1") (pinfunction "1_1") (pintype "passive"))
      (node (ref "K12") (pin "1") (pinfunction "1_1") (pintype "passive"))
      (node (ref "K13") (pin "1") (pinfunction "1_1") (pintype "passive"))
      (node (ref "K14") (pin "1") (pinfunction "1_1") (pintype "passive"))
      (node (ref "K15") (pin "1") (pinfunction "1_1") (pintype "passive"))
      (node (ref "K16") (pin "1") (pinfunction "1_1") (pintype "passive"))
      (node (ref "K17") (pin "1") (pinfunction "1_1") (pintype "passive"))
      (node (ref "K18") (pin "1") (pinfunction "1_1") (pintype "passive"))
      (node (ref "K19") (pin "1") (pinfunction "1_1") (pintype "passive"))
      (node (ref "K2") (pin "1") (pinfunction "1_1") (pintype "passive"))
      (node (ref "K20") (pin "1") (pinfunction "1_1") (pintype "passive"))
      (node (ref "K21") (pin "1") (pinfunction "1_1") (pintype "passive"))
      (node (ref "K22") (pin "1") (pinfunction "1_1") (pintype "passive"))
      (node (ref "K23") (pin "1") (pinfunction "1_1") (pintype "passive"))
      (node (ref "K24") (pin "1") (pinfunction "1_1") (pintype "passive"))
      (node (ref "K3") (pin "1") (pinfunction "1_1") (pintype "passive"))
      (node (ref "K4") (pin "1") (pinfunction "1_1") (pintype "passive"))
      (node (ref "K5") (pin "1") (pinfunction "1_1") (pintype "passive"))
      (node (ref "K6") (pin "1") (pinfunction "1_1") (pintype "passive"))
      (node (ref "K7") (pin "1") (pinfunction "1_1") (pintype "passive"))
      (node (ref "K8") (pin "1") (pinfunction "1_1") (pintype "passive"))
      (node (ref "K9") (pin "1") (pinfunction "1_1") (pintype "passive"))
      (node (ref "P19") (pin "2") (pinfunction "2_2") (pintype "passive"))
    )
    (net (code "4") (name "/328P RX") (class "Default")
      (node (ref "U1") (pin "2") (pinfunction "PD0_RXD_2") (pintype "passive"))
      (node (ref "U16") (pin "3") (pinfunction "RXD_3") (pintype "passive"))
    )
    (net (code "5") (name "/328P TX") (class "Default")
      (node (ref "U1") (pin "3") (pinfunction "PD1_TXD_3") (pintype "passive"))
      (node (ref "U16") (pin "2") (pinfunction "TXD_2") (pintype "passive"))
    )
    (net (code "6") (name "/channel1") (class "Default")
      (node (ref "R1") (pin "2") (pinfunction "2_2") (pintype "passive"))
      (node (ref "R2") (pin "2") (pinfunction "2_2") (pintype "passive"))
      (node (ref "U1") (pin "4") (pinfunction "INT0_PD2_4") (pintype "passive"))
    )
    (net (code "7") (name "/channel2") (class "Default")
      (node (ref "R3") (pin "2") (pinfunction "2_2") (pintype "passive"))
      (node (ref "R4") (pin "2") (pinfunction "2_2") (pintype "passive"))
      (node (ref "U1") (pin "5") (pinfunction "INT1_PD3_5") (pintype "passive"))
    )
    (net (code "8") (name "/channel3") (class "Default")
      (node (ref "R5") (pin "2") (pinfunction "2_2") (pintype "passive"))
      (node (ref "R6") (pin "2") (pinfunction "2_2") (pintype "passive"))
      (node (ref "U1") (pin "6") (pinfunction "T0_PD4_6") (pintype "passive"))
    )
    (net (code "9") (name "/channel4") (class "Default")
      (node (ref "R7") (pin "2") (pinfunction "2_2") (pintype "passive"))
      (node (ref "R8") (pin "2") (pinfunction "2_2") (pintype "passive"))
      (node (ref "U1") (pin "11") (pinfunction "T1_PD5_11") (pintype "passive"))
    )
    (net (code "10") (name "/channel5") (class "Default")
      (node (ref "R10") (pin "2") (pinfunction "2_2") (pintype "passive"))
      (node (ref "R9") (pin "2") (pinfunction "2_2") (pintype "passive"))
      (node (ref "U1") (pin "12") (pinfunction "AIN0_PD6_12") (pintype "passive"))
    )
    (net (code "11") (name "/channel6") (class "Default")
      (node (ref "R11") (pin "2") (pinfunction "2_2") (pintype "passive"))
      (node (ref "R12") (pin "2") (pinfunction "2_2") (pintype "passive"))
      (node (ref "U1") (pin "13") (pinfunction "AIN1_PD7_13") (pintype "passive"))
    )
    (net (code "12") (name "/channel7") (class "Default")
      (node (ref "R13") (pin "2") (pinfunction "2_2") (pintype "passive"))
      (node (ref "R14") (pin "2") (pinfunction "2_2") (pintype "passive"))
      (node (ref "U1") (pin "14") (pinfunction "PCINT0_PB0_14") (pintype "passive"))
    )
    (net (code "13") (name "/channel8") (class "Default")
      (node (ref "R15") (pin "2") (pinfunction "2_2") (pintype "passive"))
      (node (ref "R16") (pin "2") (pinfunction "2_2") (pintype "passive"))
      (node (ref "U1") (pin "15") (pinfunction "PCINT1__PB1_15") (pintype "passive"))
    )
    (net (code "14") (name "/channel9") (class "Default")
      (node (ref "R17") (pin "2") (pinfunction "2_2") (pintype "passive"))
      (node (ref "R18") (pin "2") (pinfunction "2_2") (pintype "passive"))
      (node (ref "U1") (pin "16") (pinfunction "PCINT2_PB2_16") (pintype "passive"))
    )
    (net (code "15") (name "/channel10") (class "Default")
      (node (ref "R19") (pin "2") (pinfunction "2_2") (pintype "passive"))
      (node (ref "R20") (pin "2") (pinfunction "2_2") (pintype "passive"))
      (node (ref "U1") (pin "17") (pinfunction "PCINT3_PB3_17") (pintype "passive"))
    )
    (net (code "16") (name "/channel11") (class "Default")
      (node (ref "R21") (pin "2") (pinfunction "2_2") (pintype "passive"))
      (node (ref "R22") (pin "2") (pinfunction "2_2") (pintype "passive"))
    )
    (net (code "17") (name "/channel12") (class "Default")
      (node (ref "R23") (pin "2") (pinfunction "2_2") (pintype "passive"))
      (node (ref "R26") (pin "2") (pinfunction "2_2") (pintype "passive"))
    )
    (net (code "18") (name "/eps8266 3.3V RX") (class "Default")
      (node (ref "H1") (pin "8") (pinfunction "8_8") (pintype "passive"))
      (node (ref "Q26") (pin "1") (pinfunction "S_1") (pintype "passive"))
      (node (ref "R33") (pin "1") (pinfunction "1_1") (pintype "passive"))
    )
    (net (code "19") (name "/eps8266 3.3V TX") (class "Default")
      (node (ref "H1") (pin "1") (pinfunction "1_1") (pintype "passive"))
      (node (ref "Q25") (pin "1") (pinfunction "S_1") (pintype "passive"))
      (node (ref "R30") (pin "1") (pinfunction "1_1") (pintype "passive"))
    )
    (net (code "20") (name "/eps8266 5V RX") (class "Default")
      (node (ref "Q26") (pin "3") (pinfunction "D_3") (pintype "passive"))
      (node (ref "R32") (pin "1") (pinfunction "1_1") (pintype "passive"))
      (node (ref "U1") (pin "24") (pinfunction "PC1_ADC1_24") (pintype "passive"))
    )
    (net (code "21") (name "/eps8266 5V TX") (class "Default")
      (node (ref "Q25") (pin "3") (pinfunction "D_3") (pintype "passive"))
      (node (ref "R31") (pin "1") (pinfunction "1_1") (pintype "passive"))
      (node (ref "U1") (pin "23") (pinfunction "PC0_ADC0_23") (pintype "passive"))
    )
    (net (code "22") (name "/line1") (class "Default")
      (node (ref "K1") (pin "5") (pinfunction "5_5") (pintype "passive"))
      (node (ref "K10") (pin "5") (pinfunction "5_5") (pintype "passive"))
      (node (ref "K11") (pin "5") (pinfunction "5_5") (pintype "passive"))
      (node (ref "K13") (pin "5") (pinfunction "5_5") (pintype "passive"))
      (node (ref "K15") (pin "5") (pinfunction "5_5") (pintype "passive"))
      (node (ref "K17") (pin "5") (pinfunction "5_5") (pintype "passive"))
      (node (ref "K19") (pin "5") (pinfunction "5_5") (pintype "passive"))
      (node (ref "K21") (pin "5") (pinfunction "5_5") (pintype "passive"))
      (node (ref "K23") (pin "5") (pinfunction "5_5") (pintype "passive"))
      (node (ref "K4") (pin "5") (pinfunction "5_5") (pintype "passive"))
      (node (ref "K6") (pin "5") (pinfunction "5_5") (pintype "passive"))
      (node (ref "K8") (pin "5") (pinfunction "5_5") (pintype "passive"))
      (node (ref "P18") (pin "1") (pinfunction "1_1") (pintype "passive"))
    )
    (net (code "23") (name "/line2") (class "Default")
      (node (ref "K12") (pin "5") (pinfunction "5_5") (pintype "passive"))
      (node (ref "K14") (pin "5") (pinfunction "5_5") (pintype "passive"))
      (node (ref "K16") (pin "5") (pinfunction "5_5") (pintype "passive"))
      (node (ref "K18") (pin "5") (pinfunction "5_5") (pintype "passive"))
      (node (ref "K2") (pin "5") (pinfunction "5_5") (pintype "passive"))
      (node (ref "K20") (pin "5") (pinfunction "5_5") (pintype "passive"))
      (node (ref "K22") (pin "5") (pinfunction "5_5") (pintype "passive"))
      (node (ref "K24") (pin "5") (pinfunction "5_5") (pintype "passive"))
      (node (ref "K3") (pin "5") (pinfunction "5_5") (pintype "passive"))
      (node (ref "K5") (pin "5") (pinfunction "5_5") (pintype "passive"))
      (node (ref "K7") (pin "5") (pinfunction "5_5") (pintype "passive"))
      (node (ref "K9") (pin "5") (pinfunction "5_5") (pintype "passive"))
      (node (ref "P18") (pin "2") (pinfunction "2_2") (pintype "passive"))
    )
    (net (code "24") (name "GND") (class "Default")
      (node (ref "C1") (pin "1") (pinfunction "1_1") (pintype "passive"))
      (node (ref "C2") (pin "1") (pinfunction "1_1") (pintype "passive"))
      (node (ref "C3") (pin "2") (pinfunction "2_2") (pintype "passive"))
      (node (ref "C4") (pin "2") (pinfunction "2_2") (pintype "passive"))
      (node (ref "C5") (pin "1") (pinfunction "1_1") (pintype "passive"))
      (node (ref "C6") (pin "2") (pinfunction "2_2") (pintype "passive"))
      (node (ref "C7") (pin "2") (pinfunction "2_2") (pintype "passive"))
      (node (ref "C8") (pin "1") (pinfunction "1_1") (pintype "passive"))
      (node (ref "C9") (pin "1") (pinfunction "1_1") (pintype "passive"))
      (node (ref "H1") (pin "2") (pinfunction "2_2") (pintype "passive"))
      (node (ref "KEY1") (pin "1") (pinfunction "1_1") (pintype "passive"))
      (node (ref "KEY1") (pin "2") (pinfunction "2_2") (pintype "passive"))
      (node (ref "P17") (pin "2") (pinfunction "2_2") (pintype "passive"))
      (node (ref "P19") (pin "1") (pinfunction "1_1") (pintype "passive"))
      (node (ref "Q1") (pin "1") (pinfunction "E_1") (pintype "passive"))
      (node (ref "Q10") (pin "1") (pinfunction "E_1") (pintype "passive"))
      (node (ref "Q11") (pin "1") (pinfunction "E_1") (pintype "passive"))
      (node (ref "Q12") (pin "1") (pinfunction "E_1") (pintype "passive"))
      (node (ref "Q13") (pin "1") (pinfunction "E_1") (pintype "passive"))
      (node (ref "Q14") (pin "1") (pinfunction "E_1") (pintype "passive"))
      (node (ref "Q15") (pin "1") (pinfunction "E_1") (pintype "passive"))
      (node (ref "Q16") (pin "1") (pinfunction "E_1") (pintype "passive"))
      (node (ref "Q17") (pin "1") (pinfunction "E_1") (pintype "passive"))
      (node (ref "Q18") (pin "1") (pinfunction "E_1") (pintype "passive"))
      (node (ref "Q19") (pin "1") (pinfunction "E_1") (pintype "passive"))
      (node (ref "Q2") (pin "1") (pinfunction "E_1") (pintype "passive"))
      (node (ref "Q20") (pin "1") (pinfunction "E_1") (pintype "passive"))
      (node (ref "Q21") (pin "1") (pinfunction "E_1") (pintype "passive"))
      (node (ref "Q22") (pin "1") (pinfunction "E_1") (pintype "passive"))
      (node (ref "Q23") (pin "1") (pinfunction "E_1") (pintype "passive"))
      (node (ref "Q24") (pin "1") (pinfunction "E_1") (pintype "passive"))
      (node (ref "Q3") (pin "1") (pinfunction "E_1") (pintype "passive"))
      (node (ref "Q4") (pin "1") (pinfunction "E_1") (pintype "passive"))
      (node (ref "Q5") (pin "1") (pinfunction "E_1") (pintype "passive"))
      (node (ref "Q6") (pin "1") (pinfunction "E_1") (pintype "passive"))
      (node (ref "Q7") (pin "1") (pinfunction "E_1") (pintype "passive"))
      (node (ref "Q8") (pin "1") (pinfunction "E_1") (pintype "passive"))
      (node (ref "Q9") (pin "1") (pinfunction "E_1") (pintype "passive"))
      (node (ref "R24") (pin "2") (pinfunction "2_2") (pintype "passive"))
      (node (ref "R29") (pin "2") (pinfunction "2_2") (pintype "passive"))
      (node (ref "U1") (pin "22") (pinfunction "GND_22") (pintype "passive"))
      (node (ref "U1") (pin "8") (pinfunction "GND_8") (pintype "passive"))
      (node (ref "U16") (pin "1") (pinfunction "GND_1") (pintype "passive"))
      (node (ref "U2") (pin "2") (pinfunction "GND_2") (pintype "passive"))
      (node (ref "USB1") (pin "5") (pinfunction "GND_5") (pintype "passive"))
    )
    (net (code "25") (name "Net-(D1-A)") (class "Default")
      (node (ref "D1") (pin "2") (pinfunction "A_2") (pintype "passive"))
      (node (ref "K1") (pin "4") (pinfunction "4_4") (pintype "passive"))
      (node (ref "Q1") (pin "3") (pinfunction "C_3") (pintype "passive"))
    )
    (net (code "26") (name "Net-(D2-A)") (class "Default")
      (node (ref "D2") (pin "2") (pinfunction "A_2") (pintype "passive"))
      (node (ref "K2") (pin "4") (pinfunction "4_4") (pintype "passive"))
      (node (ref "Q2") (pin "3") (pinfunction "C_3") (pintype "passive"))
    )
    (net (code "27") (name "Net-(D3-A)") (class "Default")
      (node (ref "D3") (pin "2") (pinfunction "A_2") (pintype "passive"))
      (node (ref "K3") (pin "4") (pinfunction "4_4") (pintype "passive"))
      (node (ref "Q3") (pin "3") (pinfunction "C_3") (pintype "passive"))
    )
    (net (code "28") (name "Net-(D4-A)") (class "Default")
      (node (ref "D4") (pin "2") (pinfunction "A_2") (pintype "passive"))
      (node (ref "K4") (pin "4") (pinfunction "4_4") (pintype "passive"))
      (node (ref "Q4") (pin "3") (pinfunction "C_3") (pintype "passive"))
    )
    (net (code "29") (name "Net-(D5-A)") (class "Default")
      (node (ref "D5") (pin "2") (pinfunction "A_2") (pintype "passive"))
      (node (ref "K5") (pin "4") (pinfunction "4_4") (pintype "passive"))
      (node (ref "Q5") (pin "3") (pinfunction "C_3") (pintype "passive"))
    )
    (net (code "30") (name "Net-(D6-A)") (class "Default")
      (node (ref "D6") (pin "2") (pinfunction "A_2") (pintype "passive"))
      (node (ref "K6") (pin "4") (pinfunction "4_4") (pintype "passive"))
      (node (ref "Q6") (pin "3") (pinfunction "C_3") (pintype "passive"))
    )
    (net (code "31") (name "Net-(D7-A)") (class "Default")
      (node (ref "D7") (pin "2") (pinfunction "A_2") (pintype "passive"))
      (node (ref "K7") (pin "4") (pinfunction "4_4") (pintype "passive"))
      (node (ref "Q7") (pin "3") (pinfunction "C_3") (pintype "passive"))
    )
    (net (code "32") (name "Net-(D8-A)") (class "Default")
      (node (ref "D8") (pin "2") (pinfunction "A_2") (pintype "passive"))
      (node (ref "K8") (pin "4") (pinfunction "4_4") (pintype "passive"))
      (node (ref "Q8") (pin "3") (pinfunction "C_3") (pintype "passive"))
    )
    (net (code "33") (name "Net-(D9-A)") (class "Default")
      (node (ref "D9") (pin "2") (pinfunction "A_2") (pintype "passive"))
      (node (ref "K9") (pin "4") (pinfunction "4_4") (pintype "passive"))
      (node (ref "Q9") (pin "3") (pinfunction "C_3") (pintype "passive"))
    )
    (net (code "34") (name "Net-(D10-A)") (class "Default")
      (node (ref "D10") (pin "2") (pinfunction "A_2") (pintype "passive"))
      (node (ref "K10") (pin "4") (pinfunction "4_4") (pintype "passive"))
      (node (ref "Q10") (pin "3") (pinfunction "C_3") (pintype "passive"))
    )
    (net (code "35") (name "Net-(D11-A)") (class "Default")
      (node (ref "D11") (pin "2") (pinfunction "A_2") (pintype "passive"))
      (node (ref "K11") (pin "4") (pinfunction "4_4") (pintype "passive"))
      (node (ref "Q11") (pin "3") (pinfunction "C_3") (pintype "passive"))
    )
    (net (code "36") (name "Net-(D12-A)") (class "Default")
      (node (ref "D12") (pin "2") (pinfunction "A_2") (pintype "passive"))
      (node (ref "K12") (pin "4") (pinfunction "4_4") (pintype "passive"))
      (node (ref "Q12") (pin "3") (pinfunction "C_3") (pintype "passive"))
    )
    (net (code "37") (name "Net-(D13-A)") (class "Default")
      (node (ref "D13") (pin "2") (pinfunction "A_2") (pintype "passive"))
      (node (ref "K13") (pin "4") (pinfunction "4_4") (pintype "passive"))
      (node (ref "Q13") (pin "3") (pinfunction "C_3") (pintype "passive"))
    )
    (net (code "38") (name "Net-(D14-A)") (class "Default")
      (node (ref "D14") (pin "2") (pinfunction "A_2") (pintype "passive"))
      (node (ref "K14") (pin "4") (pinfunction "4_4") (pintype "passive"))
      (node (ref "Q14") (pin "3") (pinfunction "C_3") (pintype "passive"))
    )
    (net (code "39") (name "Net-(D15-A)") (class "Default")
      (node (ref "D15") (pin "2") (pinfunction "A_2") (pintype "passive"))
      (node (ref "K15") (pin "4") (pinfunction "4_4") (pintype "passive"))
      (node (ref "Q15") (pin "3") (pinfunction "C_3") (pintype "passive"))
    )
    (net (code "40") (name "Net-(D16-A)") (class "Default")
      (node (ref "D16") (pin "2") (pinfunction "A_2") (pintype "passive"))
      (node (ref "K16") (pin "4") (pinfunction "4_4") (pintype "passive"))
      (node (ref "Q16") (pin "3") (pinfunction "C_3") (pintype "passive"))
    )
    (net (code "41") (name "Net-(D17-A)") (class "Default")
      (node (ref "D17") (pin "2") (pinfunction "A_2") (pintype "passive"))
      (node (ref "K17") (pin "4") (pinfunction "4_4") (pintype "passive"))
      (node (ref "Q17") (pin "3") (pinfunction "C_3") (pintype "passive"))
    )
    (net (code "42") (name "Net-(D18-A)") (class "Default")
      (node (ref "D18") (pin "2") (pinfunction "A_2") (pintype "passive"))
      (node (ref "K18") (pin "4") (pinfunction "4_4") (pintype "passive"))
      (node (ref "Q18") (pin "3") (pinfunction "C_3") (pintype "passive"))
    )
    (net (code "43") (name "Net-(D19-A)") (class "Default")
      (node (ref "D19") (pin "2") (pinfunction "A_2") (pintype "passive"))
      (node (ref "K19") (pin "4") (pinfunction "4_4") (pintype "passive"))
      (node (ref "Q19") (pin "3") (pinfunction "C_3") (pintype "passive"))
    )
    (net (code "44") (name "Net-(D20-A)") (class "Default")
      (node (ref "D20") (pin "2") (pinfunction "A_2") (pintype "passive"))
      (node (ref "K20") (pin "4") (pinfunction "4_4") (pintype "passive"))
      (node (ref "Q20") (pin "3") (pinfunction "C_3") (pintype "passive"))
    )
    (net (code "45") (name "Net-(D21-A)") (class "Default")
      (node (ref "D21") (pin "2") (pinfunction "A_2") (pintype "passive"))
      (node (ref "K21") (pin "4") (pinfunction "4_4") (pintype "passive"))
      (node (ref "Q21") (pin "3") (pinfunction "C_3") (pintype "passive"))
    )
    (net (code "46") (name "Net-(D22-A)") (class "Default")
      (node (ref "D22") (pin "2") (pinfunction "A_2") (pintype "passive"))
      (node (ref "K22") (pin "4") (pinfunction "4_4") (pintype "passive"))
      (node (ref "Q22") (pin "3") (pinfunction "C_3") (pintype "passive"))
    )
    (net (code "47") (name "Net-(D23-A)") (class "Default")
      (node (ref "D23") (pin "2") (pinfunction "A_2") (pintype "passive"))
      (node (ref "K23") (pin "4") (pinfunction "4_4") (pintype "passive"))
      (node (ref "Q23") (pin "3") (pinfunction "C_3") (pintype "passive"))
    )
    (net (code "48") (name "Net-(D24-A)") (class "Default")
      (node (ref "D24") (pin "2") (pinfunction "A_2") (pintype "passive"))
      (node (ref "K24") (pin "4") (pinfunction "4_4") (pintype "passive"))
      (node (ref "Q24") (pin "3") (pinfunction "C_3") (pintype "passive"))
    )
    (net (code "49") (name "Net-(D25-A)") (class "Default")
      (node (ref "D25") (pin "2") (pinfunction "A_2") (pintype "passive"))
      (node (ref "P17") (pin "1") (pinfunction "1_1") (pintype "passive"))
    )
    (net (code "50") (name "Net-(D25-K)") (class "Default")
      (node (ref "C3") (pin "1") (pinfunction "1_1") (pintype "passive"))
      (node (ref "D25") (pin "1") (pinfunction "K_1") (pintype "passive"))
      (node (ref "U2") (pin "1") (pinfunction "IN_1") (pintype "passive"))
    )
    (net (code "51") (name "Net-(K1-Pad2)") (class "Default")
      (node (ref "K1") (pin "2") (pinfunction "2_2") (pintype "passive"))
      (node (ref "U3") (pin "1") (pinfunction "1_1") (pintype "passive"))
    )
    (net (code "52") (name "Net-(K2-Pad2)") (class "Default")
      (node (ref "K2") (pin "2") (pinfunction "2_2") (pintype "passive"))
      (node (ref "U3") (pin "2") (pinfunction "2_2") (pintype "passive"))
    )
    (net (code "53") (name "Net-(K3-Pad2)") (class "Default")
      (node (ref "K3") (pin "2") (pinfunction "2_2") (pintype "passive"))
      (node (ref "U4") (pin "2") (pinfunction "2_2") (pintype "passive"))
    )
    (net (code "54") (name "Net-(K4-Pad2)") (class "Default")
      (node (ref "K4") (pin "2") (pinfunction "2_2") (pintype "passive"))
      (node (ref "U4") (pin "1") (pinfunction "1_1") (pintype "passive"))
    )
    (net (code "55") (name "Net-(K5-Pad2)") (class "Default")
      (node (ref "K5") (pin "2") (pinfunction "2_2") (pintype "passive"))
      (node (ref "U5") (pin "2") (pinfunction "2_2") (pintype "passive"))
    )
    (net (code "56") (name "Net-(K6-Pad2)") (class "Default")
      (node (ref "K6") (pin "2") (pinfunction "2_2") (pintype "passive"))
      (node (ref "U5") (pin "1") (pinfunction "1_1") (pintype "passive"))
    )
    (net (code "57") (name "Net-(K7-Pad2)") (class "Default")
      (node (ref "K7") (pin "2") (pinfunction "2_2") (pintype "passive"))
      (node (ref "U6") (pin "2") (pinfunction "2_2") (pintype "passive"))
    )
    (net (code "58") (name "Net-(K8-Pad2)") (class "Default")
      (node (ref "K8") (pin "2") (pinfunction "2_2") (pintype "passive"))
      (node (ref "U6") (pin "1") (pinfunction "1_1") (pintype "passive"))
    )
    (net (code "59") (name "Net-(K9-Pad2)") (class "Default")
      (node (ref "K9") (pin "2") (pinfunction "2_2") (pintype "passive"))
      (node (ref "U7") (pin "2") (pinfunction "2_2") (pintype "passive"))
    )
    (net (code "60") (name "Net-(K10-Pad2)") (class "Default")
      (node (ref "K10") (pin "2") (pinfunction "2_2") (pintype "passive"))
      (node (ref "U7") (pin "1") (pinfunction "1_1") (pintype "passive"))
    )
    (net (code "61") (name "Net-(K11-Pad2)") (class "Default")
      (node (ref "K11") (pin "2") (pinfunction "2_2") (pintype "passive"))
      (node (ref "U8") (pin "1") (pinfunction "1_1") (pintype "passive"))
    )
    (net (code "62") (name "Net-(K12-Pad2)") (class "Default")
      (node (ref "K12") (pin "2") (pinfunction "2_2") (pintype "passive"))
      (node (ref "U8") (pin "2") (pinfunction "2_2") (pintype "passive"))
    )
    (net (code "63") (name "Net-(K13-Pad2)") (class "Default")
      (node (ref "K13") (pin "2") (pinfunction "2_2") (pintype "passive"))
      (node (ref "U9") (pin "1") (pinfunction "1_1") (pintype "passive"))
    )
    (net (code "64") (name "Net-(K14-Pad2)") (class "Default")
      (node (ref "K14") (pin "2") (pinfunction "2_2") (pintype "passive"))
      (node (ref "U9") (pin "2") (pinfunction "2_2") (pintype "passive"))
    )
    (net (code "65") (name "Net-(K15-Pad2)") (class "Default")
      (node (ref "K15") (pin "2") (pinfunction "2_2") (pintype "passive"))
      (node (ref "U10") (pin "1") (pinfunction "1_1") (pintype "passive"))
    )
    (net (code "66") (name "Net-(K16-Pad2)") (class "Default")
      (node (ref "K16") (pin "2") (pinfunction "2_2") (pintype "passive"))
      (node (ref "U10") (pin "2") (pinfunction "2_2") (pintype "passive"))
    )
    (net (code "67") (name "Net-(K17-Pad2)") (class "Default")
      (node (ref "K17") (pin "2") (pinfunction "2_2") (pintype "passive"))
      (node (ref "U11") (pin "1") (pinfunction "1_1") (pintype "passive"))
    )
    (net (code "68") (name "Net-(K18-Pad2)") (class "Default")
      (node (ref "K18") (pin "2") (pinfunction "2_2") (pintype "passive"))
      (node (ref "U11") (pin "2") (pinfunction "2_2") (pintype "passive"))
    )
    (net (code "69") (name "Net-(K19-Pad2)") (class "Default")
      (node (ref "K19") (pin "2") (pinfunction "2_2") (pintype "passive"))
      (node (ref "U12") (pin "1") (pinfunction "1_1") (pintype "passive"))
    )
    (net (code "70") (name "Net-(K20-Pad2)") (class "Default")
      (node (ref "K20") (pin "2") (pinfunction "2_2") (pintype "passive"))
      (node (ref "U12") (pin "2") (pinfunction "2_2") (pintype "passive"))
    )
    (net (code "71") (name "Net-(K21-Pad2)") (class "Default")
      (node (ref "K21") (pin "2") (pinfunction "2_2") (pintype "passive"))
      (node (ref "U13") (pin "1") (pinfunction "1_1") (pintype "passive"))
    )
    (net (code "72") (name "Net-(K22-Pad2)") (class "Default")
      (node (ref "K22") (pin "2") (pinfunction "2_2") (pintype "passive"))
      (node (ref "U13") (pin "2") (pinfunction "2_2") (pintype "passive"))
    )
    (net (code "73") (name "Net-(K23-Pad2)") (class "Default")
      (node (ref "K23") (pin "2") (pinfunction "2_2") (pintype "passive"))
      (node (ref "U14") (pin "1") (pinfunction "1_1") (pintype "passive"))
    )
    (net (code "74") (name "Net-(K24-Pad2)") (class "Default")
      (node (ref "K24") (pin "2") (pinfunction "2_2") (pintype "passive"))
      (node (ref "U14") (pin "2") (pinfunction "2_2") (pintype "passive"))
    )
    (net (code "75") (name "Net-(LD1-Pad2)") (class "Default")
      (node (ref "LD1") (pin "2") (pinfunction "2_2") (pintype "passive"))
      (node (ref "R24") (pin "1") (pinfunction "1_1") (pintype "passive"))
    )
    (net (code "76") (name "Net-(Q1-B)") (class "Default")
      (node (ref "Q1") (pin "2") (pinfunction "B_2") (pintype "passive"))
      (node (ref "R1") (pin "1") (pinfunction "1_1") (pintype "passive"))
    )
    (net (code "77") (name "Net-(Q2-B)") (class "Default")
      (node (ref "Q2") (pin "2") (pinfunction "B_2") (pintype "passive"))
      (node (ref "R2") (pin "1") (pinfunction "1_1") (pintype "passive"))
    )
    (net (code "78") (name "Net-(Q3-B)") (class "Default")
      (node (ref "Q3") (pin "2") (pinfunction "B_2") (pintype "passive"))
      (node (ref "R3") (pin "1") (pinfunction "1_1") (pintype "passive"))
    )
    (net (code "79") (name "Net-(Q4-B)") (class "Default")
      (node (ref "Q4") (pin "2") (pinfunction "B_2") (pintype "passive"))
      (node (ref "R4") (pin "1") (pinfunction "1_1") (pintype "passive"))
    )
    (net (code "80") (name "Net-(Q5-B)") (class "Default")
      (node (ref "Q5") (pin "2") (pinfunction "B_2") (pintype "passive"))
      (node (ref "R5") (pin "1") (pinfunction "1_1") (pintype "passive"))
    )
    (net (code "81") (name "Net-(Q6-B)") (class "Default")
      (node (ref "Q6") (pin "2") (pinfunction "B_2") (pintype "passive"))
      (node (ref "R6") (pin "1") (pinfunction "1_1") (pintype "passive"))
    )
    (net (code "82") (name "Net-(Q7-B)") (class "Default")
      (node (ref "Q7") (pin "2") (pinfunction "B_2") (pintype "passive"))
      (node (ref "R7") (pin "1") (pinfunction "1_1") (pintype "passive"))
    )
    (net (code "83") (name "Net-(Q8-B)") (class "Default")
      (node (ref "Q8") (pin "2") (pinfunction "B_2") (pintype "passive"))
      (node (ref "R8") (pin "1") (pinfunction "1_1") (pintype "passive"))
    )
    (net (code "84") (name "Net-(Q9-B)") (class "Default")
      (node (ref "Q9") (pin "2") (pinfunction "B_2") (pintype "passive"))
      (node (ref "R9") (pin "1") (pinfunction "1_1") (pintype "passive"))
    )
    (net (code "85") (name "Net-(Q10-B)") (class "Default")
      (node (ref "Q10") (pin "2") (pinfunction "B_2") (pintype "passive"))
      (node (ref "R10") (pin "1") (pinfunction "1_1") (pintype "passive"))
    )
    (net (code "86") (name "Net-(Q11-B)") (class "Default")
      (node (ref "Q11") (pin "2") (pinfunction "B_2") (pintype "passive"))
      (node (ref "R11") (pin "1") (pinfunction "1_1") (pintype "passive"))
    )
    (net (code "87") (name "Net-(Q12-B)") (class "Default")
      (node (ref "Q12") (pin "2") (pinfunction "B_2") (pintype "passive"))
      (node (ref "R12") (pin "1") (pinfunction "1_1") (pintype "passive"))
    )
    (net (code "88") (name "Net-(Q13-B)") (class "Default")
      (node (ref "Q13") (pin "2") (pinfunction "B_2") (pintype "passive"))
      (node (ref "R13") (pin "1") (pinfunction "1_1") (pintype "passive"))
    )
    (net (code "89") (name "Net-(Q14-B)") (class "Default")
      (node (ref "Q14") (pin "2") (pinfunction "B_2") (pintype "passive"))
      (node (ref "R14") (pin "1") (pinfunction "1_1") (pintype "passive"))
    )
    (net (code "90") (name "Net-(Q15-B)") (class "Default")
      (node (ref "Q15") (pin "2") (pinfunction "B_2") (pintype "passive"))
      (node (ref "R15") (pin "1") (pinfunction "1_1") (pintype "passive"))
    )
    (net (code "91") (name "Net-(Q16-B)") (class "Default")
      (node (ref "Q16") (pin "2") (pinfunction "B_2") (pintype "passive"))
      (node (ref "R16") (pin "1") (pinfunction "1_1") (pintype "passive"))
    )
    (net (code "92") (name "Net-(Q17-B)") (class "Default")
      (node (ref "Q17") (pin "2") (pinfunction "B_2") (pintype "passive"))
      (node (ref "R17") (pin "1") (pinfunction "1_1") (pintype "passive"))
    )
    (net (code "93") (name "Net-(Q18-B)") (class "Default")
      (node (ref "Q18") (pin "2") (pinfunction "B_2") (pintype "passive"))
      (node (ref "R18") (pin "1") (pinfunction "1_1") (pintype "passive"))
    )
    (net (code "94") (name "Net-(Q19-B)") (class "Default")
      (node (ref "Q19") (pin "2") (pinfunction "B_2") (pintype "passive"))
      (node (ref "R19") (pin "1") (pinfunction "1_1") (pintype "passive"))
    )
    (net (code "95") (name "Net-(Q20-B)") (class "Default")
      (node (ref "Q20") (pin "2") (pinfunction "B_2") (pintype "passive"))
      (node (ref "R20") (pin "1") (pinfunction "1_1") (pintype "passive"))
    )
    (net (code "96") (name "Net-(Q21-B)") (class "Default")
      (node (ref "Q21") (pin "2") (pinfunction "B_2") (pintype "passive"))
      (node (ref "R21") (pin "1") (pinfunction "1_1") (pintype "passive"))
    )
    (net (code "97") (name "Net-(Q22-B)") (class "Default")
      (node (ref "Q22") (pin "2") (pinfunction "B_2") (pintype "passive"))
      (node (ref "R22") (pin "1") (pinfunction "1_1") (pintype "passive"))
    )
    (net (code "98") (name "Net-(Q23-B)") (class "Default")
      (node (ref "Q23") (pin "2") (pinfunction "B_2") (pintype "passive"))
      (node (ref "R23") (pin "1") (pinfunction "1_1") (pintype "passive"))
    )
    (net (code "99") (name "Net-(Q24-B)") (class "Default")
      (node (ref "Q24") (pin "2") (pinfunction "B_2") (pintype "passive"))
      (node (ref "R26") (pin "1") (pinfunction "1_1") (pintype "passive"))
    )
    (net (code "100") (name "Net-(R28-Pad2)") (class "Default")
      (node (ref "R28") (pin "2") (pinfunction "2_2") (pintype "passive"))
      (node (ref "R29") (pin "1") (pinfunction "1_1") (pintype "passive"))
    )
    (net (code "101") (name "Net-(U1-PB6_XTAL1)") (class "Default")
      (node (ref "C1") (pin "2") (pinfunction "2_2") (pintype "passive"))
      (node (ref "U1") (pin "9") (pinfunction "PB6_XTAL1_9") (pintype "passive"))
      (node (ref "X1") (pin "1") (pinfunction "1_1") (pintype "passive"))
    )
    (net (code "102") (name "Net-(U1-PB7_XTAL2)") (class "Default")
      (node (ref "C2") (pin "2") (pinfunction "2_2") (pintype "passive"))
      (node (ref "U1") (pin "10") (pinfunction "PB7_XTAL2_10") (pintype "passive"))
      (node (ref "X1") (pin "2") (pinfunction "2_2") (pintype "passive"))
    )
    (net (code "103") (name "Net-(U1-PC6_RESET#)") (class "Default")
      (node (ref "KEY1") (pin "3") (pinfunction "3_3") (pintype "passive"))
      (node (ref "KEY1") (pin "4") (pinfunction "4_4") (pintype "passive"))
      (node (ref "R25") (pin "1") (pinfunction "1_1") (pintype "passive"))
      (node (ref "U1") (pin "1") (pinfunction "PC6_RESET#_1") (pintype "passive"))
    )
    (net (code "104") (name "Net-(U1-PCINT5_PB5)") (class "Default")
      (node (ref "LD1") (pin "1") (pinfunction "1_1") (pintype "passive"))
      (node (ref "U1") (pin "19") (pinfunction "PCINT5_PB5_19") (pintype "passive"))
    )
    (net (code "105") (name "Net-(U15-ADJUST)") (class "Default")
      (node (ref "R27") (pin "1") (pinfunction "1_1") (pintype "passive"))
      (node (ref "R28") (pin "1") (pinfunction "1_1") (pintype "passive"))
      (node (ref "U15") (pin "1") (pinfunction "ADJUST_1") (pintype "passive"))
    )
    (net (code "106") (name "Net-(U16-UD+)") (class "Default")
      (node (ref "U16") (pin "5") (pinfunction "UD+_5") (pintype "passive"))
      (node (ref "USB1") (pin "3") (pinfunction "D+_3") (pintype "passive"))
    )
    (net (code "107") (name "Net-(U16-UD-)") (class "Default")
      (node (ref "U16") (pin "6") (pinfunction "UD-_6") (pintype "passive"))
      (node (ref "USB1") (pin "2") (pinfunction "D-_2") (pintype "passive"))
    )
    (net (code "108") (name "Net-(U16-V3)") (class "Default")
      (node (ref "C7") (pin "1") (pinfunction "1_1") (pintype "passive"))
      (node (ref "U16") (pin "4") (pinfunction "V3_4") (pintype "passive"))
    )
    (net (code "109") (name "Net-(U16-VCC)") (class "Default")
      (node (ref "U16") (pin "16") (pinfunction "VCC_16") (pintype "passive"))
      (node (ref "USB1") (pin "1") (pinfunction "VCC_1") (pintype "passive"))
    )
    (net (code "110") (name "Net-(U16-XI)") (class "Default")
      (node (ref "C8") (pin "2") (pinfunction "2_2") (pintype "passive"))
      (node (ref "U16") (pin "7") (pinfunction "XI_7") (pintype "passive"))
      (node (ref "X2") (pin "1") (pinfunction "OSC1_1") (pintype "passive"))
    )
    (net (code "111") (name "Net-(U16-XO)") (class "Default")
      (node (ref "C9") (pin "2") (pinfunction "2_2") (pintype "passive"))
      (node (ref "U16") (pin "8") (pinfunction "XO_8") (pintype "passive"))
      (node (ref "X2") (pin "2") (pinfunction "OSC2_2") (pintype "passive"))
    )
    (net (code "112") (name "unconnected-(H1-Pad3)") (class "Default")
      (node (ref "H1") (pin "3") (pinfunction "3_3") (pintype "passive+no_connect"))
    )
    (net (code "113") (name "unconnected-(H1-Pad4)") (class "Default")
      (node (ref "H1") (pin "4") (pinfunction "4_4") (pintype "passive+no_connect"))
    )
    (net (code "114") (name "unconnected-(H1-Pad5)") (class "Default")
      (node (ref "H1") (pin "5") (pinfunction "5_5") (pintype "passive+no_connect"))
    )
    (net (code "115") (name "unconnected-(H1-Pad6)") (class "Default")
      (node (ref "H1") (pin "6") (pinfunction "6_6") (pintype "passive+no_connect"))
    )
    (net (code "116") (name "unconnected-(K1-Pad3)") (class "Default")
      (node (ref "K1") (pin "3") (pinfunction "3_3") (pintype "passive+no_connect"))
    )
    (net (code "117") (name "unconnected-(K2-Pad3)") (class "Default")
      (node (ref "K2") (pin "3") (pinfunction "3_3") (pintype "passive+no_connect"))
    )
    (net (code "118") (name "unconnected-(K3-Pad3)") (class "Default")
      (node (ref "K3") (pin "3") (pinfunction "3_3") (pintype "passive+no_connect"))
    )
    (net (code "119") (name "unconnected-(K4-Pad3)") (class "Default")
      (node (ref "K4") (pin "3") (pinfunction "3_3") (pintype "passive+no_connect"))
    )
    (net (code "120") (name "unconnected-(K5-Pad3)") (class "Default")
      (node (ref "K5") (pin "3") (pinfunction "3_3") (pintype "passive+no_connect"))
    )
    (net (code "121") (name "unconnected-(K6-Pad3)") (class "Default")
      (node (ref "K6") (pin "3") (pinfunction "3_3") (pintype "passive+no_connect"))
    )
    (net (code "122") (name "unconnected-(K7-Pad3)") (class "Default")
      (node (ref "K7") (pin "3") (pinfunction "3_3") (pintype "passive+no_connect"))
    )
    (net (code "123") (name "unconnected-(K8-Pad3)") (class "Default")
      (node (ref "K8") (pin "3") (pinfunction "3_3") (pintype "passive+no_connect"))
    )
    (net (code "124") (name "unconnected-(K9-Pad3)") (class "Default")
      (node (ref "K9") (pin "3") (pinfunction "3_3") (pintype "passive+no_connect"))
    )
    (net (code "125") (name "unconnected-(K10-Pad3)") (class "Default")
      (node (ref "K10") (pin "3") (pinfunction "3_3") (pintype "passive+no_connect"))
    )
    (net (code "126") (name "unconnected-(K11-Pad3)") (class "Default")
      (node (ref "K11") (pin "3") (pinfunction "3_3") (pintype "passive+no_connect"))
    )
    (net (code "127") (name "unconnected-(K12-Pad3)") (class "Default")
      (node (ref "K12") (pin "3") (pinfunction "3_3") (pintype "passive+no_connect"))
    )
    (net (code "128") (name "unconnected-(K13-Pad3)") (class "Default")
      (node (ref "K13") (pin "3") (pinfunction "3_3") (pintype "passive+no_connect"))
    )
    (net (code "129") (name "unconnected-(K14-Pad3)") (class "Default")
      (node (ref "K14") (pin "3") (pinfunction "3_3") (pintype "passive+no_connect"))
    )
    (net (code "130") (name "unconnected-(K15-Pad3)") (class "Default")
      (node (ref "K15") (pin "3") (pinfunction "3_3") (pintype "passive+no_connect"))
    )
    (net (code "131") (name "unconnected-(K16-Pad3)") (class "Default")
      (node (ref "K16") (pin "3") (pinfunction "3_3") (pintype "passive+no_connect"))
    )
    (net (code "132") (name "unconnected-(K17-Pad3)") (class "Default")
      (node (ref "K17") (pin "3") (pinfunction "3_3") (pintype "passive+no_connect"))
    )
    (net (code "133") (name "unconnected-(K18-Pad3)") (class "Default")
      (node (ref "K18") (pin "3") (pinfunction "3_3") (pintype "passive+no_connect"))
    )
    (net (code "134") (name "unconnected-(K19-Pad3)") (class "Default")
      (node (ref "K19") (pin "3") (pinfunction "3_3") (pintype "passive+no_connect"))
    )
    (net (code "135") (name "unconnected-(K20-Pad3)") (class "Default")
      (node (ref "K20") (pin "3") (pinfunction "3_3") (pintype "passive+no_connect"))
    )
    (net (code "136") (name "unconnected-(K21-Pad3)") (class "Default")
      (node (ref "K21") (pin "3") (pinfunction "3_3") (pintype "passive+no_connect"))
    )
    (net (code "137") (name "unconnected-(K22-Pad3)") (class "Default")
      (node (ref "K22") (pin "3") (pinfunction "3_3") (pintype "passive+no_connect"))
    )
    (net (code "138") (name "unconnected-(K23-Pad3)") (class "Default")
      (node (ref "K23") (pin "3") (pinfunction "3_3") (pintype "passive+no_connect"))
    )
    (net (code "139") (name "unconnected-(K24-Pad3)") (class "Default")
      (node (ref "K24") (pin "3") (pinfunction "3_3") (pintype "passive+no_connect"))
    )
    (net (code "140") (name "unconnected-(U1-AREF-Pad21)") (class "Default")
      (node (ref "U1") (pin "21") (pinfunction "AREF_21") (pintype "passive+no_connect"))
    )
    (net (code "141") (name "unconnected-(U1-PC2_ADC2-Pad25)") (class "Default")
      (node (ref "U1") (pin "25") (pinfunction "PC2_ADC2_25") (pintype "passive+no_connect"))
    )
    (net (code "142") (name "unconnected-(U1-PC3_ADC3-Pad26)") (class "Default")
      (node (ref "U1") (pin "26") (pinfunction "PC3_ADC3_26") (pintype "passive+no_connect"))
    )
    (net (code "143") (name "unconnected-(U1-PC4_ADC4-Pad27)") (class "Default")
      (node (ref "U1") (pin "27") (pinfunction "PC4_ADC4_27") (pintype "passive+no_connect"))
    )
    (net (code "144") (name "unconnected-(U1-PC5_ADC5-Pad28)") (class "Default")
      (node (ref "U1") (pin "28") (pinfunction "PC5_ADC5_28") (pintype "passive+no_connect"))
    )
    (net (code "145") (name "unconnected-(U1-PCINT4_PB4-Pad18)") (class "Default")
      (node (ref "U1") (pin "18") (pinfunction "PCINT4_PB4_18") (pintype "passive+no_connect"))
    )
    (net (code "146") (name "unconnected-(U16-CTS#-Pad9)") (class "Default")
      (node (ref "U16") (pin "9") (pinfunction "CTS#_9") (pintype "passive+no_connect"))
    )
    (net (code "147") (name "unconnected-(U16-DCD#-Pad12)") (class "Default")
      (node (ref "U16") (pin "12") (pinfunction "DCD#_12") (pintype "passive+no_connect"))
    )
    (net (code "148") (name "unconnected-(U16-DSR#-Pad10)") (class "Default")
      (node (ref "U16") (pin "10") (pinfunction "DSR#_10") (pintype "passive+no_connect"))
    )
    (net (code "149") (name "unconnected-(U16-DTR#-Pad13)") (class "Default")
      (node (ref "U16") (pin "13") (pinfunction "DTR#_13") (pintype "passive+no_connect"))
    )
    (net (code "150") (name "unconnected-(U16-R232-Pad15)") (class "Default")
      (node (ref "U16") (pin "15") (pinfunction "R232_15") (pintype "passive+no_connect"))
    )
    (net (code "151") (name "unconnected-(U16-RI-Pad11)") (class "Default")
      (node (ref "U16") (pin "11") (pinfunction "RI_11") (pintype "passive+no_connect"))
    )
    (net (code "152") (name "unconnected-(U16-RTS#-Pad14)") (class "Default")
      (node (ref "U16") (pin "14") (pinfunction "RTS#_14") (pintype "passive+no_connect"))
    )
    (net (code "153") (name "unconnected-(USB1-DI-Pad4)") (class "Default")
      (node (ref "USB1") (pin "4") (pinfunction "DI_4") (pintype "passive+no_connect"))
    )
  )
)
